# 30000.net
KiCad netlist of a schematic drawn in EasyEDA Pro
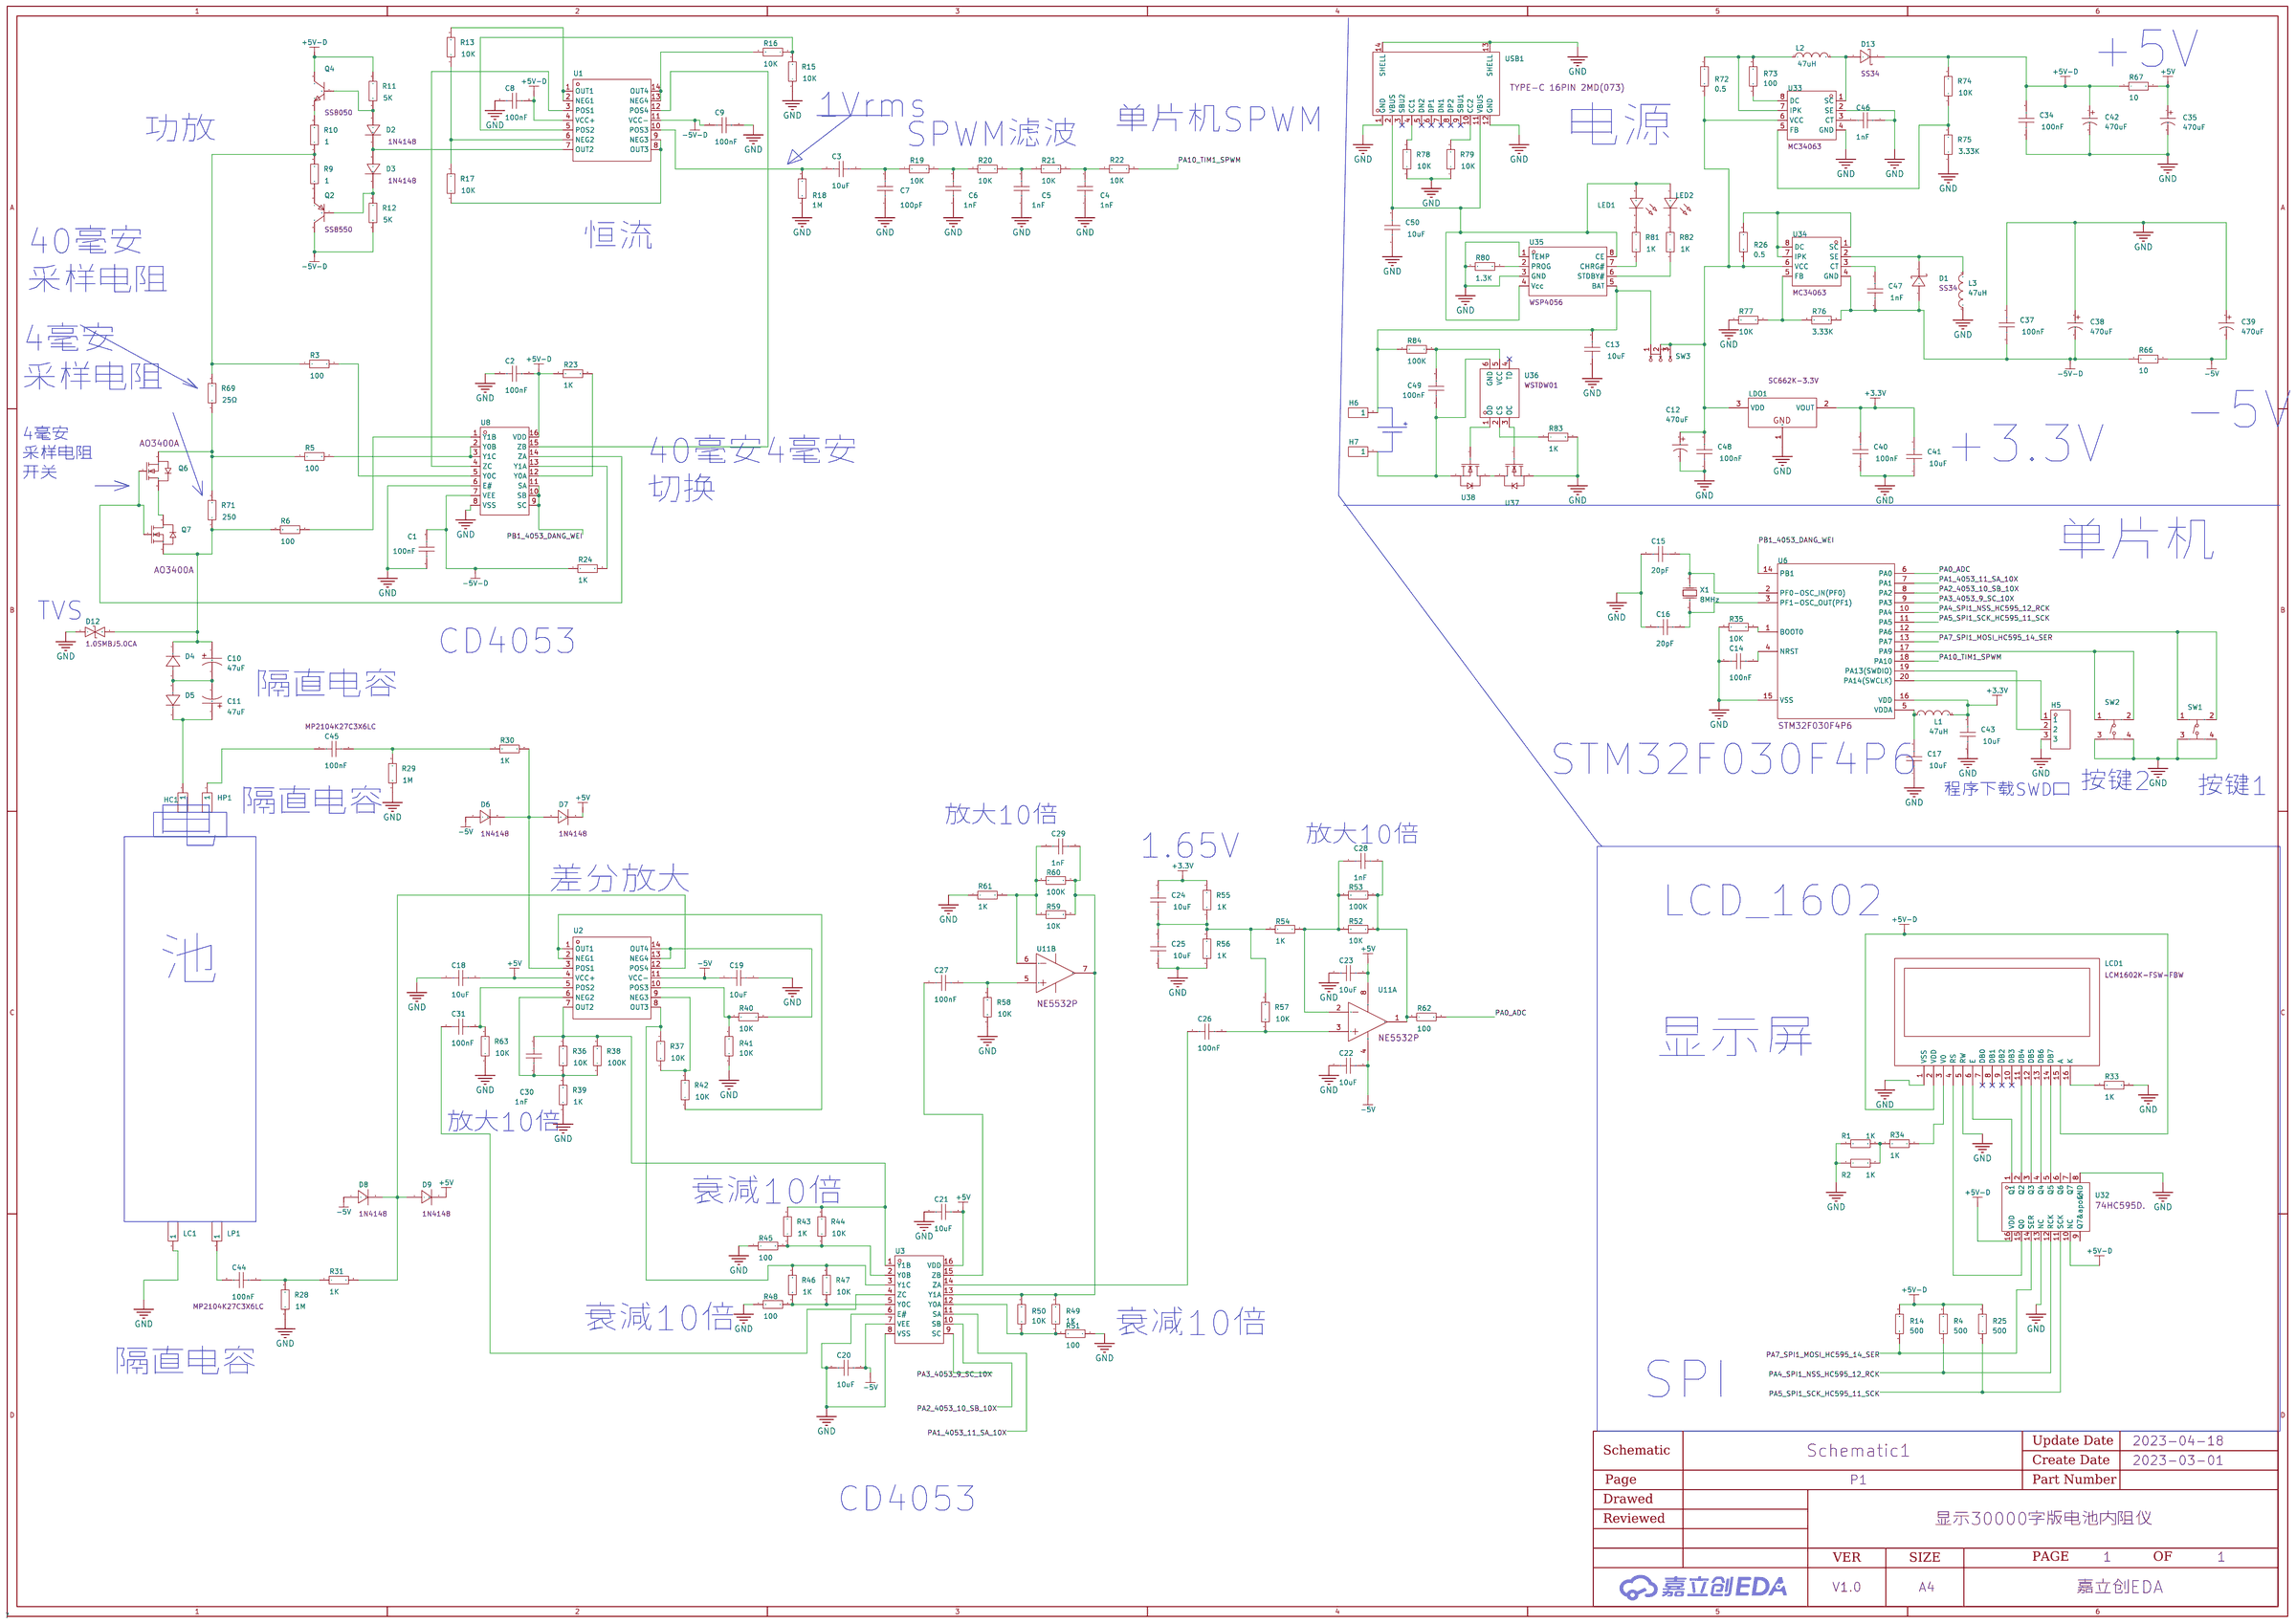
[diagram p0: schematic sheet]

(export (version "E")
  (design (tool "Eeschema 10.0.6"))
  (components
    (comp (ref "C1")
      (value "100nF")
      (footprint "easyedapro:C0603")
      (libsource (lib "easyedapro") (part "CapAcitance"))
    )
    (comp (ref "C2")
      (value "100nF")
      (footprint "easyedapro:C0603")
      (libsource (lib "easyedapro") (part "CapAcitance"))
    )
    (comp (ref "C3")
      (value "10uF")
      (footprint "easyedapro:C0603")
      (libsource (lib "easyedapro") (part "CapAcitance"))
    )
    (comp (ref "C4")
      (value "1nF")
      (footprint "easyedapro:C0603")
      (libsource (lib "easyedapro") (part "CapAcitance"))
    )
    (comp (ref "C5")
      (value "1nF")
      (footprint "easyedapro:C0603")
      (libsource (lib "easyedapro") (part "CapAcitance"))
    )
    (comp (ref "C6")
      (value "1nF")
      (footprint "easyedapro:C0603")
      (libsource (lib "easyedapro") (part "CapAcitance"))
    )
    (comp (ref "C7")
      (value "100pF")
      (footprint "easyedapro:C0603")
      (libsource (lib "easyedapro") (part "CapAcitance"))
    )
    (comp (ref "C8")
      (value "100nF")
      (footprint "easyedapro:C0603")
      (libsource (lib "easyedapro") (part "CapAcitance"))
    )
    (comp (ref "C9")
      (value "100nF")
      (footprint "easyedapro:C0603")
      (libsource (lib "easyedapro") (part "CapAcitance"))
    )
    (comp (ref "C10")
      (value "47uF")
      (footprint "easyedapro:CAP-TH_BD10.0-P5.00-D1.0-FD")
      (description "容值:47uF;精度:±20%;额定电压:200V;电容体直径:10mm;电容体长度:20mm;脚间距:5mm;工作寿命:5000hrs@105°C;")
      (fields (field (name "Manufacturer Part") "KF470M200G200A") (field (name "Manufacturer") "CapXon(丰宾)"))
      (libsource (lib "easyedapro") (part "KF470M200G200A"))
    )
    (comp (ref "C11")
      (value "47uF")
      (footprint "easyedapro:CAP-TH_BD10.0-P5.00-D1.0-FD")
      (description "容值:47uF;精度:±20%;额定电压:200V;电容体直径:10mm;电容体长度:20mm;脚间距:5mm;工作寿命:5000hrs@105°C;")
      (fields (field (name "Manufacturer Part") "KF470M200G200A") (field (name "Manufacturer") "CapXon(丰宾)"))
      (libsource (lib "easyedapro") (part "KF470M200G200A"))
    )
    (comp (ref "C12")
      (value "470uF")
      (footprint "easyedapro:CAP-TH_BD8.0-P3.50-D0.6-FD")
      (description "容值:470uF;精度:±20%;额定电压:16V;电容体直径:8mm;电容体长度:12mm;脚间距:3.5mm;工作寿命:2000hrs@105°C;")
      (fields
        (field (name "Manufacturer Part") "KM477M016F12RR0VH2FP0")
        (field (name "Manufacturer") "CX(承兴)")
      )
      (libsource (lib "easyedapro") (part "470uf16v"))
    )
    (comp (ref "C13")
      (value "10uF")
      (footprint "easyedapro:C0603")
      (libsource (lib "easyedapro") (part "CapAcitance"))
    )
    (comp (ref "C14")
      (value "100nF")
      (footprint "easyedapro:C0603")
      (libsource (lib "easyedapro") (part "CapAcitance"))
    )
    (comp (ref "C15")
      (value "20pF")
      (footprint "easyedapro:C0603")
      (libsource (lib "easyedapro") (part "CapAcitance"))
    )
    (comp (ref "C16")
      (value "20pF")
      (footprint "easyedapro:C0603")
      (libsource (lib "easyedapro") (part "CapAcitance"))
    )
    (comp (ref "C17")
      (value "10uF")
      (footprint "easyedapro:C0603")
      (libsource (lib "easyedapro") (part "CapAcitance"))
    )
    (comp (ref "C18")
      (value "10uF")
      (footprint "easyedapro:C0603")
      (libsource (lib "easyedapro") (part "CapAcitance"))
    )
    (comp (ref "C19")
      (value "10uF")
      (footprint "easyedapro:C0603")
      (libsource (lib "easyedapro") (part "CapAcitance"))
    )
    (comp (ref "C20")
      (value "10uF")
      (footprint "easyedapro:C0603")
      (libsource (lib "easyedapro") (part "CapAcitance"))
    )
    (comp (ref "C21")
      (value "10uF")
      (footprint "easyedapro:C0603")
      (libsource (lib "easyedapro") (part "CapAcitance"))
    )
    (comp (ref "C22")
      (value "10uF")
      (footprint "easyedapro:C0603")
      (libsource (lib "easyedapro") (part "CapAcitance"))
    )
    (comp (ref "C23")
      (value "10uF")
      (footprint "easyedapro:C0603")
      (libsource (lib "easyedapro") (part "CapAcitance"))
    )
    (comp (ref "C24")
      (value "10uF")
      (footprint "easyedapro:C0603")
      (libsource (lib "easyedapro") (part "CapAcitance"))
    )
    (comp (ref "C25")
      (value "10uF")
      (footprint "easyedapro:C0603")
      (libsource (lib "easyedapro") (part "CapAcitance"))
    )
    (comp (ref "C26")
      (value "100nF")
      (footprint "easyedapro:C0603")
      (libsource (lib "easyedapro") (part "CapAcitance"))
    )
    (comp (ref "C27")
      (value "100nF")
      (footprint "easyedapro:C0603")
      (libsource (lib "easyedapro") (part "CapAcitance"))
    )
    (comp (ref "C28")
      (value "1nF")
      (footprint "easyedapro:C0603")
      (libsource (lib "easyedapro") (part "CapAcitance"))
    )
    (comp (ref "C29")
      (value "1nF")
      (footprint "easyedapro:C0603")
      (libsource (lib "easyedapro") (part "CapAcitance"))
    )
    (comp (ref "C30")
      (value "1nF")
      (footprint "easyedapro:C0603")
      (libsource (lib "easyedapro") (part "CapAcitance"))
    )
    (comp (ref "C31")
      (value "100nF")
      (footprint "easyedapro:C0603")
      (libsource (lib "easyedapro") (part "CapAcitance"))
    )
    (comp (ref "C34")
      (value "100nF")
      (footprint "easyedapro:C0603")
      (libsource (lib "easyedapro") (part "CapAcitance"))
    )
    (comp (ref "C35")
      (value "470uF")
      (footprint "easyedapro:CAP-TH_BD8.0-P3.50-D0.6-FD")
      (description "容值:470uF;精度:±20%;额定电压:16V;电容体直径:8mm;电容体长度:12mm;脚间距:3.5mm;工作寿命:2000hrs@105°C;")
      (fields
        (field (name "Manufacturer Part") "KM477M016F12RR0VH2FP0")
        (field (name "Manufacturer") "CX(承兴)")
      )
      (libsource (lib "easyedapro") (part "470uf16v"))
    )
    (comp (ref "C37")
      (value "100nF")
      (footprint "easyedapro:C0603")
      (libsource (lib "easyedapro") (part "CapAcitance"))
    )
    (comp (ref "C38")
      (value "470uF")
      (footprint "easyedapro:CAP-TH_BD8.0-P3.50-D0.6-FD")
      (description "容值:470uF;精度:±20%;额定电压:16V;电容体直径:8mm;电容体长度:12mm;脚间距:3.5mm;工作寿命:2000hrs@105°C;")
      (fields
        (field (name "Manufacturer Part") "KM477M016F12RR0VH2FP0")
        (field (name "Manufacturer") "CX(承兴)")
      )
      (libsource (lib "easyedapro") (part "470uf16v"))
    )
    (comp (ref "C39")
      (value "470uF")
      (footprint "easyedapro:CAP-TH_BD8.0-P3.50-D0.6-FD")
      (description "容值:470uF;精度:±20%;额定电压:16V;电容体直径:8mm;电容体长度:12mm;脚间距:3.5mm;工作寿命:2000hrs@105°C;")
      (fields
        (field (name "Manufacturer Part") "KM477M016F12RR0VH2FP0")
        (field (name "Manufacturer") "CX(承兴)")
      )
      (libsource (lib "easyedapro") (part "470uf16v"))
    )
    (comp (ref "C40")
      (value "100nF")
      (footprint "easyedapro:C0603")
      (libsource (lib "easyedapro") (part "CapAcitance"))
    )
    (comp (ref "C41")
      (value "10uF")
      (footprint "easyedapro:C0603")
      (libsource (lib "easyedapro") (part "CapAcitance"))
    )
    (comp (ref "C42")
      (value "470uF")
      (footprint "easyedapro:CAP-TH_BD8.0-P3.50-D0.6-FD")
      (description "容值:470uF;精度:±20%;额定电压:16V;电容体直径:8mm;电容体长度:12mm;脚间距:3.5mm;工作寿命:2000hrs@105°C;")
      (fields
        (field (name "Manufacturer Part") "KM477M016F12RR0VH2FP0")
        (field (name "Manufacturer") "CX(承兴)")
      )
      (libsource (lib "easyedapro") (part "470uf16v"))
    )
    (comp (ref "C43")
      (value "10uF")
      (footprint "easyedapro:C0603")
      (libsource (lib "easyedapro") (part "CapAcitance"))
    )
    (comp (ref "C44")
      (value "100nF")
      (footprint "easyedapro:CAP-TH_L13.0-W6.0-P10.00-D1.0")
      (description "等级:X2;容值:100nF;精度:±10%;")
      (fields (field (name "Manufacturer Part") "MP2104K27C3X6LC") (field (name "Manufacturer") "SRD(圣融达)"))
      (libsource (lib "easyedapro") (part "MP2104KGC3XLC"))
    )
    (comp (ref "C45")
      (value "100nF")
      (footprint "easyedapro:CAP-TH_L13.0-W6.0-P10.00-D1.0")
      (description "等级:X2;容值:100nF;精度:±10%;")
      (fields (field (name "Manufacturer Part") "MP2104K27C3X6LC") (field (name "Manufacturer") "SRD(圣融达)"))
      (libsource (lib "easyedapro") (part "MP2104KGC3XLC"))
    )
    (comp (ref "C46")
      (value "1nF")
      (footprint "easyedapro:C0603")
      (libsource (lib "easyedapro") (part "CapAcitance"))
    )
    (comp (ref "C47")
      (value "1nF")
      (footprint "easyedapro:C0603")
      (libsource (lib "easyedapro") (part "CapAcitance"))
    )
    (comp (ref "C48")
      (value "100nF")
      (footprint "easyedapro:C0603")
      (libsource (lib "easyedapro") (part "CapAcitance"))
    )
    (comp (ref "C49")
      (value "100nF")
      (footprint "easyedapro:C0603")
      (libsource (lib "easyedapro") (part "CapAcitance"))
    )
    (comp (ref "C50")
      (value "10uF")
      (footprint "easyedapro:C0603")
      (libsource (lib "easyedapro") (part "CapAcitance"))
    )
    (comp (ref "D1")
      (value "SS34")
      (footprint "easyedapro:SMA_L4.3-W2.6-LS5.2-RD")
      (description "二极管配置:独立式;直流反向耐压(Vr):40V;平均整流电流(Io):3A;正向压降(Vf):550mV@3A;反向电流(Ir):500uA@40V;")
      (fields (field (name "Manufacturer Part") "SS34") (field (name "Manufacturer") "MDD"))
      (libsource (lib "easyedapro") (part "SS34_C8678"))
    )
    (comp (ref "D2")
      (value "1N4148")
      (footprint "easyedapro:DO-35_BD2.0-L4.0-P8.00-D0.5-FD")
      (fields (field (name "Manufacturer Part") "1N4148") (field (name "Manufacturer") "ST(先科)"))
      (libsource (lib "easyedapro") (part "1N4148"))
    )
    (comp (ref "D3")
      (value "1N4148")
      (footprint "easyedapro:DO-35_BD2.0-L4.0-P8.00-D0.5-FD")
      (fields (field (name "Manufacturer Part") "1N4148") (field (name "Manufacturer") "ST(先科)"))
      (libsource (lib "easyedapro") (part "1N4148"))
    )
    (comp (ref "D4")
      (value "~")
      (footprint "easyedapro:DO_1N4007")
      (libsource (lib "easyedapro") (part "D_1N4007"))
    )
    (comp (ref "D5")
      (value "~")
      (footprint "easyedapro:DO_1N4007")
      (libsource (lib "easyedapro") (part "D_1N4007"))
    )
    (comp (ref "D6")
      (value "1N4148")
      (footprint "easyedapro:DO-35_BD2.0-L4.0-P8.00-D0.5-FD")
      (fields (field (name "Manufacturer Part") "1N4148") (field (name "Manufacturer") "ST(先科)"))
      (libsource (lib "easyedapro") (part "1N4148"))
    )
    (comp (ref "D7")
      (value "1N4148")
      (footprint "easyedapro:DO-35_BD2.0-L4.0-P8.00-D0.5-FD")
      (fields (field (name "Manufacturer Part") "1N4148") (field (name "Manufacturer") "ST(先科)"))
      (libsource (lib "easyedapro") (part "1N4148"))
    )
    (comp (ref "D8")
      (value "1N4148")
      (footprint "easyedapro:DO-35_BD2.0-L4.0-P8.00-D0.5-FD")
      (fields (field (name "Manufacturer Part") "1N4148") (field (name "Manufacturer") "ST(先科)"))
      (libsource (lib "easyedapro") (part "1N4148"))
    )
    (comp (ref "D9")
      (value "1N4148")
      (footprint "easyedapro:DO-35_BD2.0-L4.0-P8.00-D0.5-FD")
      (fields (field (name "Manufacturer Part") "1N4148") (field (name "Manufacturer") "ST(先科)"))
      (libsource (lib "easyedapro") (part "1N4148"))
    )
    (comp (ref "D12")
      (value "1.0SMBJ5.0CA")
      (footprint "easyedapro:SMB_L4.6-W3.6-LS5.3-BI")
      (description "极性:双向;反向截止电压(Vrwm):5V;击穿电压:6.4V;峰值脉冲电流(Ipp)@10/1000s:108.7A;最大钳位电压:9.2V;")
      (fields (field (name "Manufacturer Part") "1.0SMBJ5.0CA") (field (name "Manufacturer") "BORN(伯恩半导体)"))
      (libsource (lib "easyedapro") (part "1.0SMBJ5.0CA"))
    )
    (comp (ref "D13")
      (value "SS34")
      (footprint "easyedapro:SMA_L4.3-W2.6-LS5.2-RD")
      (description "二极管配置:独立式;直流反向耐压(Vr):40V;平均整流电流(Io):3A;正向压降(Vf):550mV@3A;反向电流(Ir):500uA@40V;")
      (fields (field (name "Manufacturer Part") "SS34") (field (name "Manufacturer") "MDD"))
      (libsource (lib "easyedapro") (part "SS34_C8678"))
    )
    (comp (ref "H5")
      (value "~")
      (footprint "easyedapro:HDR-TH_3P-P2.54-V-M")
      (libsource (lib "easyedapro") (part "PZ254V-11-03P_C2937625"))
    )
    (comp (ref "H6")
      (value "~")
      (footprint "easyedapro:HDR-TH_1P-V-M_XKB_X4611WV-01I-C28D40")
      (libsource (lib "easyedapro") (part "HDR_1x1"))
    )
    (comp (ref "H7")
      (value "~")
      (footprint "easyedapro:HDR-TH_1P-V-M_XKB_X4611WV-01I-C28D40")
      (libsource (lib "easyedapro") (part "HDR_1x1"))
    )
    (comp (ref "HC1")
      (value "~")
      (footprint "easyedapro:HDR-TH_1P-V-M_XKB_X4611WV-01I-C28D40")
      (libsource (lib "easyedapro") (part "HDR_1x1"))
    )
    (comp (ref "HP1")
      (value "~")
      (footprint "easyedapro:HDR-TH_1P-V-M_XKB_X4611WV-01I-C28D40")
      (libsource (lib "easyedapro") (part "HDR_1x1"))
    )
    (comp (ref "L1")
      (value "47uH")
      (footprint "easyedapro:IND-SMD_L4.5-W4.0_SLF0403")
      (description "电感值:47uH;直流电阻(DCR):844mΩ;精度:±10%;额定电流:540mA;")
      (fields
        (field (name "Manufacturer Part") "SLF0403-470KTT")
        (field (name "Manufacturer") "Sunltech(韩国顺磁)")
      )
      (libsource (lib "easyedapro") (part "SLF0403-470KTT"))
    )
    (comp (ref "L2")
      (value "47uH")
      (footprint "easyedapro:IND-SMD_L4.5-W4.0_SLF0403")
      (description "电感值:47uH;直流电阻(DCR):844mΩ;精度:±10%;额定电流:540mA;")
      (fields
        (field (name "Manufacturer Part") "SLF0403-470KTT")
        (field (name "Manufacturer") "Sunltech(韩国顺磁)")
      )
      (libsource (lib "easyedapro") (part "SLF0403-470KTT"))
    )
    (comp (ref "L3")
      (value "47uH")
      (footprint "easyedapro:IND-SMD_L4.5-W4.0_SLF0403")
      (description "电感值:47uH;直流电阻(DCR):844mΩ;精度:±10%;额定电流:540mA;")
      (fields
        (field (name "Manufacturer Part") "SLF0403-470KTT")
        (field (name "Manufacturer") "Sunltech(韩国顺磁)")
      )
      (libsource (lib "easyedapro") (part "SLF0403-470KTT"))
    )
    (comp (ref "LC1")
      (value "~")
      (footprint "easyedapro:HDR-TH_1P-V-M_XKB_X4611WV-01I-C28D40")
      (libsource (lib "easyedapro") (part "HDR_1x1"))
    )
    (comp (ref "LCD1")
      (value "LCM1602K-FSW-FBW")
      (footprint "easyedapro:MODULE-TH_LCM1602K")
      (description "尺寸(inch):-;主控芯片:KS0066U;")
      (fields
        (field (name "Manufacturer Part") "LCM1602K-FSW-FBW")
        (field (name "Manufacturer") "LONTECH(厦门龙特)")
      )
      (libsource (lib "easyedapro") (part "LCM1602K-FSW-FBW"))
    )
    (comp (ref "LDO1")
      (value "SC662K-3.3V")
      (footprint "easyedapro:SOT-23-3_L2.9-W1.3-P1.90-LS2.4-BR")
      (description "输出类型:固定;输出极性:正;最大输入电压:6V;输出电压:3.3V;输出电流:250mA;电源纹波抑制比(PSRR):50dB@(1kHz);")
      (fields (field (name "Manufacturer Part") "SC662K-3.3V") (field (name "Manufacturer") "FM(富满)"))
      (libsource (lib "easyedapro") (part "SC662K-3.3V"))
    )
    (comp (ref "LED1")
      (value "~")
      (footprint "easyedapro:LED_TH-3mm")
      (libsource (lib "easyedapro") (part "LED_TH-R"))
    )
    (comp (ref "LED2")
      (value "~")
      (footprint "easyedapro:LED_TH-3mm")
      (libsource (lib "easyedapro") (part "LED_TH-R"))
    )
    (comp (ref "LP1")
      (value "~")
      (footprint "easyedapro:HDR-TH_1P-V-M_XKB_X4611WV-01I-C28D40")
      (libsource (lib "easyedapro") (part "HDR_1x1"))
    )
    (comp (ref "Q2")
      (value "SS8550")
      (footprint "easyedapro:SOT-23-3_L2.9-W1.6-P1.90-LS2.8-BR")
      (fields (field (name "Manufacturer Part") "SS8550") (field (name "Manufacturer") "ElecSuper(静芯微）"))
      (libsource (lib "easyedapro") (part "SS8550_C5249677"))
    )
    (comp (ref "Q4")
      (value "SS8050")
      (footprint "easyedapro:SOT-23-3_L2.9-W1.6-P1.90-LS2.8-BR")
      (fields (field (name "Manufacturer Part") "SS8050") (field (name "Manufacturer") "ElecSuper(静芯微）"))
      (libsource (lib "easyedapro") (part "SS8050_C5249676"))
    )
    (comp (ref "Q6")
      (value "AO3400A")
      (footprint "easyedapro:SOT-23-3_L2.9-W1.3-P1.90-LS2.4-BR")
      (fields (field (name "Manufacturer Part") "AO3400A") (field (name "Manufacturer") "UMW(广东友台半导体)"))
      (libsource (lib "easyedapro") (part "AO3400A_C347475"))
    )
    (comp (ref "Q7")
      (value "AO3400A")
      (footprint "easyedapro:SOT-23-3_L2.9-W1.3-P1.90-LS2.4-BR")
      (fields (field (name "Manufacturer Part") "AO3400A") (field (name "Manufacturer") "UMW(广东友台半导体)"))
      (libsource (lib "easyedapro") (part "AO3400A_C347475"))
    )
    (comp (ref "R1")
      (value "1K")
      (footprint "easyedapro:Res_1/8W")
      (libsource (lib "easyedapro") (part "电阻"))
    )
    (comp (ref "R2")
      (value "1K")
      (footprint "easyedapro:Res_1/8W")
      (libsource (lib "easyedapro") (part "电阻"))
    )
    (comp (ref "R3")
      (value "100")
      (footprint "easyedapro:Res_1/8W")
      (libsource (lib "easyedapro") (part "电阻"))
    )
    (comp (ref "R4")
      (value "500")
      (footprint "easyedapro:Res_1/8W")
      (libsource (lib "easyedapro") (part "电阻"))
    )
    (comp (ref "R5")
      (value "100")
      (footprint "easyedapro:Res_1/8W")
      (libsource (lib "easyedapro") (part "电阻"))
    )
    (comp (ref "R6")
      (value "100")
      (footprint "easyedapro:Res_1/8W")
      (libsource (lib "easyedapro") (part "电阻"))
    )
    (comp (ref "R9") (value "1") (footprint "easyedapro:Res_1/8W") (libsource (lib "easyedapro") (part "电阻")))
    (comp (ref "R10")
      (value "1")
      (footprint "easyedapro:Res_1/8W")
      (libsource (lib "easyedapro") (part "电阻"))
    )
    (comp (ref "R11")
      (value "5K")
      (footprint "easyedapro:Res_1/8W")
      (libsource (lib "easyedapro") (part "电阻"))
    )
    (comp (ref "R12")
      (value "5K")
      (footprint "easyedapro:Res_1/8W")
      (libsource (lib "easyedapro") (part "电阻"))
    )
    (comp (ref "R13")
      (value "10K")
      (footprint "easyedapro:Res_1/8W")
      (libsource (lib "easyedapro") (part "电阻"))
    )
    (comp (ref "R14")
      (value "500")
      (footprint "easyedapro:Res_1/8W")
      (libsource (lib "easyedapro") (part "电阻"))
    )
    (comp (ref "R15")
      (value "10K")
      (footprint "easyedapro:Res_1/8W")
      (libsource (lib "easyedapro") (part "电阻"))
    )
    (comp (ref "R16")
      (value "10K")
      (footprint "easyedapro:Res_1/8W")
      (libsource (lib "easyedapro") (part "电阻"))
    )
    (comp (ref "R17")
      (value "10K")
      (footprint "easyedapro:Res_1/8W")
      (libsource (lib "easyedapro") (part "电阻"))
    )
    (comp (ref "R18")
      (value "1M")
      (footprint "easyedapro:Res_1/8W")
      (libsource (lib "easyedapro") (part "电阻"))
    )
    (comp (ref "R19")
      (value "10K")
      (footprint "easyedapro:Res_1/8W")
      (libsource (lib "easyedapro") (part "电阻"))
    )
    (comp (ref "R20")
      (value "10K")
      (footprint "easyedapro:Res_1/8W")
      (libsource (lib "easyedapro") (part "电阻"))
    )
    (comp (ref "R21")
      (value "10K")
      (footprint "easyedapro:Res_1/8W")
      (libsource (lib "easyedapro") (part "电阻"))
    )
    (comp (ref "R22")
      (value "10K")
      (footprint "easyedapro:Res_1/8W")
      (libsource (lib "easyedapro") (part "电阻"))
    )
    (comp (ref "R23")
      (value "1K")
      (footprint "easyedapro:Res_1/8W")
      (libsource (lib "easyedapro") (part "电阻"))
    )
    (comp (ref "R24")
      (value "1K")
      (footprint "easyedapro:Res_1/8W")
      (libsource (lib "easyedapro") (part "电阻"))
    )
    (comp (ref "R25")
      (value "500")
      (footprint "easyedapro:Res_1/8W")
      (libsource (lib "easyedapro") (part "电阻"))
    )
    (comp (ref "R26") (value "0.5") (footprint "easyedapro:R0603") (libsource (lib "easyedapro") (part "电阻")))
    (comp (ref "R28")
      (value "1M")
      (footprint "easyedapro:Res_1/8W")
      (libsource (lib "easyedapro") (part "电阻"))
    )
    (comp (ref "R29")
      (value "1M")
      (footprint "easyedapro:Res_1/8W")
      (libsource (lib "easyedapro") (part "电阻"))
    )
    (comp (ref "R30")
      (value "1K")
      (footprint "easyedapro:Res_1/8W")
      (libsource (lib "easyedapro") (part "电阻"))
    )
    (comp (ref "R31")
      (value "1K")
      (footprint "easyedapro:Res_1/8W")
      (libsource (lib "easyedapro") (part "电阻"))
    )
    (comp (ref "R33")
      (value "1K")
      (footprint "easyedapro:Res_1/8W")
      (libsource (lib "easyedapro") (part "电阻"))
    )
    (comp (ref "R34")
      (value "1K")
      (footprint "easyedapro:Res_1/8W")
      (libsource (lib "easyedapro") (part "电阻"))
    )
    (comp (ref "R35")
      (value "10K")
      (footprint "easyedapro:Res_1/8W")
      (libsource (lib "easyedapro") (part "电阻"))
    )
    (comp (ref "R36")
      (value "10K")
      (footprint "easyedapro:Res_1/8W")
      (libsource (lib "easyedapro") (part "电阻"))
    )
    (comp (ref "R37")
      (value "10K")
      (footprint "easyedapro:Res_1/8W")
      (libsource (lib "easyedapro") (part "电阻"))
    )
    (comp (ref "R38")
      (value "100K")
      (footprint "easyedapro:Res_1/8W")
      (libsource (lib "easyedapro") (part "电阻"))
    )
    (comp (ref "R39")
      (value "1K")
      (footprint "easyedapro:Res_1/8W")
      (libsource (lib "easyedapro") (part "电阻"))
    )
    (comp (ref "R40")
      (value "10K")
      (footprint "easyedapro:Res_1/8W")
      (libsource (lib "easyedapro") (part "电阻"))
    )
    (comp (ref "R41")
      (value "10K")
      (footprint "easyedapro:Res_1/8W")
      (libsource (lib "easyedapro") (part "电阻"))
    )
    (comp (ref "R42")
      (value "10K")
      (footprint "easyedapro:Res_1/8W")
      (libsource (lib "easyedapro") (part "电阻"))
    )
    (comp (ref "R43")
      (value "1K")
      (footprint "easyedapro:Res_1/8W")
      (libsource (lib "easyedapro") (part "电阻"))
    )
    (comp (ref "R44")
      (value "10K")
      (footprint "easyedapro:Res_1/8W")
      (libsource (lib "easyedapro") (part "电阻"))
    )
    (comp (ref "R45")
      (value "100")
      (footprint "easyedapro:Res_1/8W")
      (libsource (lib "easyedapro") (part "电阻"))
    )
    (comp (ref "R46")
      (value "1K")
      (footprint "easyedapro:Res_1/8W")
      (libsource (lib "easyedapro") (part "电阻"))
    )
    (comp (ref "R47")
      (value "10K")
      (footprint "easyedapro:Res_1/8W")
      (libsource (lib "easyedapro") (part "电阻"))
    )
    (comp (ref "R48")
      (value "100")
      (footprint "easyedapro:Res_1/8W")
      (libsource (lib "easyedapro") (part "电阻"))
    )
    (comp (ref "R49")
      (value "1K")
      (footprint "easyedapro:Res_1/8W")
      (libsource (lib "easyedapro") (part "电阻"))
    )
    (comp (ref "R50")
      (value "10K")
      (footprint "easyedapro:Res_1/8W")
      (libsource (lib "easyedapro") (part "电阻"))
    )
    (comp (ref "R51")
      (value "100")
      (footprint "easyedapro:Res_1/8W")
      (libsource (lib "easyedapro") (part "电阻"))
    )
    (comp (ref "R52")
      (value "10K")
      (footprint "easyedapro:Res_1/8W")
      (libsource (lib "easyedapro") (part "电阻"))
    )
    (comp (ref "R53")
      (value "100K")
      (footprint "easyedapro:Res_1/8W")
      (libsource (lib "easyedapro") (part "电阻"))
    )
    (comp (ref "R54")
      (value "1K")
      (footprint "easyedapro:Res_1/8W")
      (libsource (lib "easyedapro") (part "电阻"))
    )
    (comp (ref "R55")
      (value "1K")
      (footprint "easyedapro:Res_1/8W")
      (libsource (lib "easyedapro") (part "电阻"))
    )
    (comp (ref "R56")
      (value "1K")
      (footprint "easyedapro:Res_1/8W")
      (libsource (lib "easyedapro") (part "电阻"))
    )
    (comp (ref "R57")
      (value "10K")
      (footprint "easyedapro:Res_1/8W")
      (libsource (lib "easyedapro") (part "电阻"))
    )
    (comp (ref "R58")
      (value "10K")
      (footprint "easyedapro:Res_1/8W")
      (libsource (lib "easyedapro") (part "电阻"))
    )
    (comp (ref "R59")
      (value "10K")
      (footprint "easyedapro:Res_1/8W")
      (libsource (lib "easyedapro") (part "电阻"))
    )
    (comp (ref "R60")
      (value "100K")
      (footprint "easyedapro:Res_1/8W")
      (libsource (lib "easyedapro") (part "电阻"))
    )
    (comp (ref "R61")
      (value "1K")
      (footprint "easyedapro:Res_1/8W")
      (libsource (lib "easyedapro") (part "电阻"))
    )
    (comp (ref "R62")
      (value "100")
      (footprint "easyedapro:Res_1/8W")
      (libsource (lib "easyedapro") (part "电阻"))
    )
    (comp (ref "R63")
      (value "10K")
      (footprint "easyedapro:Res_1/8W")
      (libsource (lib "easyedapro") (part "电阻"))
    )
    (comp (ref "R66") (value "10") (footprint "easyedapro:R0603") (libsource (lib "easyedapro") (part "电阻")))
    (comp (ref "R67") (value "10") (footprint "easyedapro:R0603") (libsource (lib "easyedapro") (part "电阻")))
    (comp (ref "R69")
      (value "25Ω")
      (footprint "easyedapro:R2512")
      (description "电阻类型:厚膜电阻;阻值:10Ω;精度:±5%;功率:2W;温度系数:±200ppm/°C;最大工作电压:200V;工作温度范围:-55°C~+155°C;")
      (fields (field (name "Manufacturer Part") "RC2512JK-7W10RL") (field (name "Manufacturer") "YAGEO(国巨)"))
      (libsource (lib "easyedapro") (part "RC2512JK-7W10RL"))
    )
    (comp (ref "R71")
      (value "250")
      (footprint "easyedapro:R0603")
      (description "电阻类型:厚膜电阻;阻值:100Ω;精度:±1%;功率:100mW;温度系数:±100ppm/°C;最大工作电压:75V;工作温度范围:-55°C~+155°C;")
      (fields (field (name "Manufacturer Part") "AC0603FR-07100RL") (field (name "Manufacturer") "YAGEO(国巨)"))
      (libsource (lib "easyedapro") (part "AC0603FR-07100RL"))
    )
    (comp (ref "R72") (value "0.5") (footprint "easyedapro:R0603") (libsource (lib "easyedapro") (part "电阻")))
    (comp (ref "R73") (value "100") (footprint "easyedapro:R0603") (libsource (lib "easyedapro") (part "电阻")))
    (comp (ref "R74") (value "10K") (footprint "easyedapro:R0603") (libsource (lib "easyedapro") (part "电阻")))
    (comp (ref "R75")
      (value "3.33K")
      (footprint "easyedapro:R0603")
      (libsource (lib "easyedapro") (part "电阻"))
    )
    (comp (ref "R76")
      (value "3.33K")
      (footprint "easyedapro:R0603")
      (libsource (lib "easyedapro") (part "电阻"))
    )
    (comp (ref "R77") (value "10K") (footprint "easyedapro:R0603") (libsource (lib "easyedapro") (part "电阻")))
    (comp (ref "R78") (value "10K") (footprint "easyedapro:R0603") (libsource (lib "easyedapro") (part "电阻")))
    (comp (ref "R79") (value "10K") (footprint "easyedapro:R0603") (libsource (lib "easyedapro") (part "电阻")))
    (comp (ref "R80")
      (value "1.3K")
      (footprint "easyedapro:R0603")
      (libsource (lib "easyedapro") (part "电阻"))
    )
    (comp (ref "R81") (value "1K") (footprint "easyedapro:R0603") (libsource (lib "easyedapro") (part "电阻")))
    (comp (ref "R82") (value "1K") (footprint "easyedapro:R0603") (libsource (lib "easyedapro") (part "电阻")))
    (comp (ref "R83") (value "1K") (footprint "easyedapro:R0603") (libsource (lib "easyedapro") (part "电阻")))
    (comp (ref "R84")
      (value "100K")
      (footprint "easyedapro:R0603")
      (libsource (lib "easyedapro") (part "电阻"))
    )
    (comp (ref "SW1")
      (value "1TS005A-2600-5001")
      (footprint "easyedapro:SW-TH_4P-L6.0-W6.0-P4.50-LS6.5")
      (fields (field (name "Manufacturer") "HYP(鸿源精密)"))
      (libsource (lib "easyedapro") (part "1TS005A-2600-5001"))
    )
    (comp (ref "SW2")
      (value "1TS005A-2600-5001")
      (footprint "easyedapro:SW-TH_4P-L6.0-W6.0-P4.50-LS6.5")
      (fields (field (name "Manufacturer") "HYP(鸿源精密)"))
      (libsource (lib "easyedapro") (part "1TS005A-2600-5001"))
    )
    (comp (ref "SW3")
      (value "SS-12F20-G070")
      (footprint "easyedapro:SW-TH_G-SWITCH_SS-12F20-G070")
      (fields (field (name "Manufacturer") "G-Switch(品赞)"))
      (libsource (lib "easyedapro") (part "SS-12F20-G070"))
    )
    (comp (ref "U1")
      (value "TL084CN")
      (footprint "easyedapro:DIP-14_L17.8-W10.2-P2.54-BL")
      (description "运放类型:J-FET;放大器组数:4;增益带宽积（GBP）:4MHz;压摆率（SR）:16 V/us;电源电压:6V ~ 36V, ±3V ~ 18V;各通道供电电流:1.4mA;")
      (fields (field (name "Manufacturer") "TI(德州仪器)"))
      (libsource (lib "easyedapro") (part "TL084CN_C54501"))
    )
    (comp (ref "U2")
      (value "TL084CN")
      (footprint "easyedapro:DIP-14_L17.8-W10.2-P2.54-BL")
      (description "运放类型:J-FET;放大器组数:4;增益带宽积（GBP）:4MHz;压摆率（SR）:16 V/us;电源电压:6V ~ 36V, ±3V ~ 18V;各通道供电电流:1.4mA;")
      (fields (field (name "Manufacturer") "TI(德州仪器)"))
      (libsource (lib "easyedapro") (part "TL084CN_C54501"))
    )
    (comp (ref "U3")
      (value "CD4053BM/TR")
      (footprint "easyedapro:SOP-16_L9.9-W3.9-P1.27-LS6.1-BL")
      (fields (field (name "Manufacturer") "HGSEMI(华冠)"))
      (libsource (lib "easyedapro") (part "CD4053BM/TR"))
    )
    (comp (ref "U6")
      (value "STM32F030F4P6")
      (footprint "easyedapro:TSSOP-20_L6.5-W4.4-P0.65-LS6.4-BL")
      (fields (field (name "Manufacturer Part") "STM32F030F4P6") (field (name "Manufacturer") "ST(意法半导体)"))
      (libsource (lib "easyedapro") (part "STM32F030F4P6"))
    )
    (comp (ref "U8")
      (value "CD4053BM/TR")
      (footprint "easyedapro:SOP-16_L9.9-W3.9-P1.27-LS6.1-BL")
      (fields (field (name "Manufacturer") "HGSEMI(华冠)"))
      (libsource (lib "easyedapro") (part "CD4053BM/TR"))
    )
    (comp (ref "U11")
      (value "NE5532P")
      (footprint "easyedapro:DIP-8_L9.4-W6.4-P2.54-LS9.1-BL")
      (description "运放类型:General Purpose;放大器组数:2;增益带宽积（GBP）:10MHz;压摆率（SR）:9 V/us;电源电压:±5V ~ 15V;各通道供电电流:8mA;")
      (fields (field (name "Manufacturer Part") "NE5532P") (field (name "Manufacturer") "TI(德州仪器)"))
      (libsource (lib "easyedapro") (part "NE5532P"))
    )
    (comp (ref "U32")
      (value "74HC595D.")
      (footprint "easyedapro:SOP-16_L9.9-W3.9-P1.27-LS6.0-BL")
      (fields (field (name "Manufacturer Part") "74HC595D.") (field (name "Manufacturer") "FM(富满)"))
      (libsource (lib "easyedapro") (part "74HC595D."))
    )
    (comp (ref "U33")
      (value "MC34063")
      (footprint "easyedapro:SOIC-8_L5.0-W4.0-P1.27-LS6.0-BL")
      (fields (field (name "Manufacturer Part") "MC34063") (field (name "Manufacturer") "HXY MOSFET(华轩阳电子)"))
      (libsource (lib "easyedapro") (part "MC34063_C5349988"))
    )
    (comp (ref "U34")
      (value "MC34063")
      (footprint "easyedapro:SOIC-8_L5.0-W4.0-P1.27-LS6.0-BL")
      (fields (field (name "Manufacturer Part") "MC34063") (field (name "Manufacturer") "HXY MOSFET(华轩阳电子)"))
      (libsource (lib "easyedapro") (part "MC34063_C5349988"))
    )
    (comp (ref "U35")
      (value "WSP4056")
      (footprint "easyedapro:SOP-8_L5.1-W3.9-P1.27-LS6.0-BL")
      (fields (field (name "Manufacturer Part") "WSP4056") (field (name "Manufacturer") "WINSOK(微硕)"))
      (libsource (lib "easyedapro") (part "WSP4056"))
    )
    (comp (ref "U36")
      (value "WSTDW01")
      (footprint "easyedapro:SOT-23-6_L2.9-W1.6-P0.95-LS2.8-BR")
      (description "充电电池的类型:-;电池单元组数:-;最大充电电流:-;充满的电池组电压:-;最大供应电压:-;")
      (fields (field (name "Manufacturer Part") "WSTDW01") (field (name "Manufacturer") "WINSOK(微硕)"))
      (libsource (lib "easyedapro") (part "WSTDW01"))
    )
    (comp (ref "U37")
      (value "AO3400A")
      (footprint "easyedapro:SOT-23-3_L3.0-W1.6-P1.90-LS2.8-BR")
      (fields (field (name "Manufacturer") "ElecSuper(静芯微）"))
      (libsource (lib "easyedapro") (part "AO3400A_C5224194"))
    )
    (comp (ref "U38")
      (value "AO3400A")
      (footprint "easyedapro:SOT-23-3_L3.0-W1.6-P1.90-LS2.8-BR")
      (fields (field (name "Manufacturer") "ElecSuper(静芯微）"))
      (libsource (lib "easyedapro") (part "AO3400A_C5224194"))
    )
    (comp (ref "USB1")
      (value "TYPE-C 16PIN 2MD(073)")
      (footprint "easyedapro:USB-C-SMD_TYPE-C-6PIN-2MD-073")
      (description "连接器类型:Type-C;标准:-;公母:母座;触点数量:16;端口数量:1;安装方式:卧贴;额定电流 - 电源:5A;工作温度范围:-25°C~+85°C;")
      (fields
        (field (name "Manufacturer Part") "TYPE-C 16PIN 2MD(073)")
        (field (name "Manufacturer") "SHOU HAN(首韩)")
      )
      (libsource (lib "easyedapro") (part "TYPE-C 16PIN 2MD(073)"))
    )
    (comp (ref "X1")
      (value "8MHz")
      (footprint "easyedapro:OSC-TH_L10.0-W4.5-P5.00")
      (description "晶振类型:49S晶振;频率:8MHz;频率公差:±20ppm;频率稳定度:±30ppm;负载电容:20pF;工作温度:-20°C~+70°C;")
      (fields (field (name "Manufacturer Part") "X49SD8MSD2SC") (field (name "Manufacturer") "YXC(扬兴晶振)"))
      (libsource (lib "easyedapro") (part "X49SD8MSD2SC"))
    )
  )
  (nets
    (net (code "1") (name "+3.3V") (class "Default")
      (node (ref "C24") (pin "2") (pinfunction "2_2") (pintype "input"))
      (node (ref "C40") (pin "2") (pinfunction "2_2") (pintype "input"))
      (node (ref "C41") (pin "2") (pinfunction "2_2") (pintype "input"))
      (node (ref "C43") (pin "2") (pinfunction "2_2") (pintype "input"))
      (node (ref "L1") (pin "2") (pinfunction "2_2") (pintype "input"))
      (node (ref "LDO1") (pin "2") (pinfunction "VOUT_2") (pintype "input"))
      (node (ref "R55") (pin "2") (pinfunction "2_2") (pintype "input"))
      (node (ref "U6") (pin "16") (pinfunction "VDD_16") (pintype "input"))
    )
    (net (code "2") (name "+5V") (class "Default")
      (node (ref "C18") (pin "2") (pinfunction "2_2") (pintype "input"))
      (node (ref "C21") (pin "2") (pinfunction "2_2") (pintype "input"))
      (node (ref "C23") (pin "2") (pinfunction "2_2") (pintype "input"))
      (node (ref "C35") (pin "1") (pinfunction "1_1") (pintype "input"))
      (node (ref "D7") (pin "2") (pinfunction "C_2") (pintype "input"))
      (node (ref "D9") (pin "2") (pinfunction "C_2") (pintype "input"))
      (node (ref "R67") (pin "2") (pinfunction "2_2") (pintype "input"))
      (node (ref "U11") (pin "8") (pinfunction "VCC+_8") (pintype "input"))
      (node (ref "U2") (pin "4") (pinfunction "VCC+_4") (pintype "input"))
      (node (ref "U3") (pin "16") (pinfunction "VDD_16") (pintype "input"))
    )
    (net (code "3") (name "+5V-D") (class "Default")
      (node (ref "C2") (pin "2") (pinfunction "2_2") (pintype "input"))
      (node (ref "C34") (pin "2") (pinfunction "2_2") (pintype "input"))
      (node (ref "C42") (pin "1") (pinfunction "1_1") (pintype "input"))
      (node (ref "C8") (pin "2") (pinfunction "2_2") (pintype "input"))
      (node (ref "D13") (pin "1") (pinfunction "K_1") (pintype "input"))
      (node (ref "LCD1") (pin "15") (pinfunction "A_15") (pintype "input"))
      (node (ref "LCD1") (pin "2") (pinfunction "VDD_2") (pintype "input"))
      (node (ref "Q4") (pin "3") (pinfunction "C_3") (pintype "input"))
      (node (ref "R11") (pin "2") (pinfunction "2_2") (pintype "input"))
      (node (ref "R14") (pin "2") (pinfunction "2_2") (pintype "input"))
      (node (ref "R23") (pin "1") (pinfunction "1_1") (pintype "input"))
      (node (ref "R25") (pin "2") (pinfunction "2_2") (pintype "input"))
      (node (ref "R4") (pin "2") (pinfunction "2_2") (pintype "input"))
      (node (ref "R67") (pin "1") (pinfunction "1_1") (pintype "input"))
      (node (ref "R74") (pin "2") (pinfunction "2_2") (pintype "input"))
      (node (ref "U1") (pin "4") (pinfunction "VCC+_4") (pintype "input"))
      (node (ref "U32") (pin "10") (pinfunction "NC_10") (pintype "input"))
      (node (ref "U32") (pin "16") (pinfunction "VDD_16") (pintype "input"))
      (node (ref "U8") (pin "16") (pinfunction "VDD_16") (pintype "input"))
    )
    (net (code "4") (name "-5V") (class "Default")
      (node (ref "C19") (pin "1") (pinfunction "1_1") (pintype "input"))
      (node (ref "C20") (pin "2") (pinfunction "2_2") (pintype "input"))
      (node (ref "C22") (pin "2") (pinfunction "2_2") (pintype "input"))
      (node (ref "C39") (pin "2") (pinfunction "2_2") (pintype "input"))
      (node (ref "D6") (pin "1") (pinfunction "A_1") (pintype "input"))
      (node (ref "D8") (pin "1") (pinfunction "A_1") (pintype "input"))
      (node (ref "R66") (pin "2") (pinfunction "2_2") (pintype "input"))
      (node (ref "U11") (pin "4") (pinfunction "VCC-_4") (pintype "input"))
      (node (ref "U2") (pin "11") (pinfunction "VCC-_11") (pintype "input"))
      (node (ref "U3") (pin "7") (pinfunction "VEE_7") (pintype "input"))
    )
    (net (code "5") (name "-5V-D") (class "Default")
      (node (ref "C1") (pin "2") (pinfunction "2_2") (pintype "input"))
      (node (ref "C37") (pin "1") (pinfunction "1_1") (pintype "input"))
      (node (ref "C38") (pin "2") (pinfunction "2_2") (pintype "input"))
      (node (ref "C47") (pin "1") (pinfunction "1_1") (pintype "input"))
      (node (ref "C9") (pin "1") (pinfunction "1_1") (pintype "input"))
      (node (ref "D1") (pin "2") (pinfunction "A_2") (pintype "input"))
      (node (ref "Q2") (pin "3") (pinfunction "C_3") (pintype "input"))
      (node (ref "R12") (pin "1") (pinfunction "1_1") (pintype "input"))
      (node (ref "R24") (pin "1") (pinfunction "1_1") (pintype "input"))
      (node (ref "R66") (pin "1") (pinfunction "1_1") (pintype "input"))
      (node (ref "R76") (pin "2") (pinfunction "2_2") (pintype "input"))
      (node (ref "U1") (pin "11") (pinfunction "VCC-_11") (pintype "input"))
      (node (ref "U34") (pin "4") (pinfunction "GND_4") (pintype "input"))
      (node (ref "U8") (pin "7") (pinfunction "VEE_7") (pintype "input"))
    )
    (net (code "6") (name "/PA0_ADC") (class "Default")
      (node (ref "R62") (pin "2") (pinfunction "2_2") (pintype "input"))
      (node (ref "U6") (pin "6") (pinfunction "PA0_6") (pintype "bidirectional"))
    )
    (net (code "7") (name "/PA1_4053_11_SA_10X") (class "Default")
      (node (ref "U3") (pin "11") (pinfunction "SA_11") (pintype "input"))
      (node (ref "U6") (pin "7") (pinfunction "PA1_7") (pintype "bidirectional"))
    )
    (net (code "8") (name "/PA2_4053_10_SB_10X") (class "Default")
      (node (ref "U3") (pin "10") (pinfunction "SB_10") (pintype "input"))
      (node (ref "U6") (pin "8") (pinfunction "PA2_8") (pintype "bidirectional"))
    )
    (net (code "9") (name "/PA3_4053_9_SC_10X") (class "Default")
      (node (ref "U3") (pin "9") (pinfunction "SC_9") (pintype "input"))
      (node (ref "U6") (pin "9") (pinfunction "PA3_9") (pintype "bidirectional"))
    )
    (net (code "10") (name "/PA4_SPI1_NSS_HC595_12_RCK") (class "Default")
      (node (ref "R4") (pin "1") (pinfunction "1_1") (pintype "input"))
      (node (ref "U32") (pin "12") (pinfunction "RCK_12") (pintype "input"))
      (node (ref "U6") (pin "10") (pinfunction "PA4_10") (pintype "bidirectional"))
    )
    (net (code "11") (name "/PA5_SPI1_SCK_HC595_11_SCK") (class "Default")
      (node (ref "R25") (pin "1") (pinfunction "1_1") (pintype "input"))
      (node (ref "U32") (pin "11") (pinfunction "SCK_11") (pintype "input"))
      (node (ref "U6") (pin "11") (pinfunction "PA5_11") (pintype "bidirectional"))
    )
    (net (code "12") (name "/PA7_SPI1_MOSI_HC595_14_SER") (class "Default")
      (node (ref "R14") (pin "1") (pinfunction "1_1") (pintype "input"))
      (node (ref "U32") (pin "14") (pinfunction "SER_14") (pintype "input"))
      (node (ref "U6") (pin "13") (pinfunction "PA7_13") (pintype "bidirectional"))
    )
    (net (code "13") (name "/PA10_TIM1_SPWM") (class "Default")
      (node (ref "R22") (pin "2") (pinfunction "2_2") (pintype "input"))
      (node (ref "U6") (pin "18") (pinfunction "PA10_18") (pintype "bidirectional"))
    )
    (net (code "14") (name "/PB1_4053_DANG_WEI") (class "Default")
      (node (ref "U6") (pin "14") (pinfunction "PB1_14") (pintype "bidirectional"))
      (node (ref "U8") (pin "10") (pinfunction "SB_10") (pintype "input"))
      (node (ref "U8") (pin "11") (pinfunction "SA_11") (pintype "input"))
      (node (ref "U8") (pin "9") (pinfunction "SC_9") (pintype "input"))
    )
    (net (code "15") (name "GND") (class "Default")
      (node (ref "C1") (pin "1") (pinfunction "1_1") (pintype "input"))
      (node (ref "C12") (pin "2") (pinfunction "2_2") (pintype "input"))
      (node (ref "C13") (pin "1") (pinfunction "1_1") (pintype "input"))
      (node (ref "C14") (pin "2") (pinfunction "2_2") (pintype "input"))
      (node (ref "C15") (pin "2") (pinfunction "2_2") (pintype "input"))
      (node (ref "C16") (pin "2") (pinfunction "2_2") (pintype "input"))
      (node (ref "C17") (pin "1") (pinfunction "1_1") (pintype "input"))
      (node (ref "C18") (pin "1") (pinfunction "1_1") (pintype "input"))
      (node (ref "C19") (pin "2") (pinfunction "2_2") (pintype "input"))
      (node (ref "C2") (pin "1") (pinfunction "1_1") (pintype "input"))
      (node (ref "C20") (pin "1") (pinfunction "1_1") (pintype "input"))
      (node (ref "C21") (pin "1") (pinfunction "1_1") (pintype "input"))
      (node (ref "C22") (pin "1") (pinfunction "1_1") (pintype "input"))
      (node (ref "C23") (pin "1") (pinfunction "1_1") (pintype "input"))
      (node (ref "C25") (pin "1") (pinfunction "1_1") (pintype "input"))
      (node (ref "C34") (pin "1") (pinfunction "1_1") (pintype "input"))
      (node (ref "C35") (pin "2") (pinfunction "2_2") (pintype "input"))
      (node (ref "C37") (pin "2") (pinfunction "2_2") (pintype "input"))
      (node (ref "C38") (pin "1") (pinfunction "1_1") (pintype "input"))
      (node (ref "C39") (pin "1") (pinfunction "1_1") (pintype "input"))
      (node (ref "C4") (pin "1") (pinfunction "1_1") (pintype "input"))
      (node (ref "C40") (pin "1") (pinfunction "1_1") (pintype "input"))
      (node (ref "C41") (pin "1") (pinfunction "1_1") (pintype "input"))
      (node (ref "C42") (pin "2") (pinfunction "2_2") (pintype "input"))
      (node (ref "C43") (pin "1") (pinfunction "1_1") (pintype "input"))
      (node (ref "C46") (pin "2") (pinfunction "2_2") (pintype "input"))
      (node (ref "C48") (pin "1") (pinfunction "1_1") (pintype "input"))
      (node (ref "C5") (pin "1") (pinfunction "1_1") (pintype "input"))
      (node (ref "C50") (pin "1") (pinfunction "1_1") (pintype "input"))
      (node (ref "C6") (pin "1") (pinfunction "1_1") (pintype "input"))
      (node (ref "C7") (pin "1") (pinfunction "1_1") (pintype "input"))
      (node (ref "C8") (pin "1") (pinfunction "1_1") (pintype "input"))
      (node (ref "C9") (pin "2") (pinfunction "2_2") (pintype "input"))
      (node (ref "D12") (pin "1") (pinfunction "1_1") (pintype "input"))
      (node (ref "H5") (pin "3") (pinfunction "3_3") (pintype "input"))
      (node (ref "L3") (pin "1") (pinfunction "1_1") (pintype "input"))
      (node (ref "LC1") (pin "1") (pinfunction "1_1") (pintype "unspecified"))
      (node (ref "LCD1") (pin "1") (pinfunction "VSS_1") (pintype "input"))
      (node (ref "LCD1") (pin "5") (pinfunction "RW_5") (pintype "input"))
      (node (ref "LDO1") (pin "1") (pinfunction "GND_1") (pintype "input"))
      (node (ref "R1") (pin "1") (pinfunction "1_1") (pintype "input"))
      (node (ref "R15") (pin "1") (pinfunction "1_1") (pintype "input"))
      (node (ref "R18") (pin "1") (pinfunction "1_1") (pintype "input"))
      (node (ref "R2") (pin "1") (pinfunction "1_1") (pintype "input"))
      (node (ref "R28") (pin "1") (pinfunction "1_1") (pintype "input"))
      (node (ref "R29") (pin "1") (pinfunction "1_1") (pintype "input"))
      (node (ref "R33") (pin "2") (pinfunction "2_2") (pintype "input"))
      (node (ref "R35") (pin "2") (pinfunction "2_2") (pintype "input"))
      (node (ref "R39") (pin "1") (pinfunction "1_1") (pintype "input"))
      (node (ref "R41") (pin "1") (pinfunction "1_1") (pintype "input"))
      (node (ref "R45") (pin "1") (pinfunction "1_1") (pintype "input"))
      (node (ref "R48") (pin "1") (pinfunction "1_1") (pintype "input"))
      (node (ref "R51") (pin "1") (pinfunction "1_1") (pintype "input"))
      (node (ref "R56") (pin "1") (pinfunction "1_1") (pintype "input"))
      (node (ref "R58") (pin "1") (pinfunction "1_1") (pintype "input"))
      (node (ref "R61") (pin "1") (pinfunction "1_1") (pintype "input"))
      (node (ref "R63") (pin "1") (pinfunction "1_1") (pintype "input"))
      (node (ref "R75") (pin "1") (pinfunction "1_1") (pintype "input"))
      (node (ref "R77") (pin "1") (pinfunction "1_1") (pintype "input"))
      (node (ref "R78") (pin "1") (pinfunction "1_1") (pintype "input"))
      (node (ref "R79") (pin "1") (pinfunction "1_1") (pintype "input"))
      (node (ref "R80") (pin "1") (pinfunction "1_1") (pintype "input"))
      (node (ref "R83") (pin "2") (pinfunction "2_2") (pintype "input"))
      (node (ref "SW1") (pin "3") (pinfunction "3_3") (pintype "input"))
      (node (ref "SW1") (pin "4") (pinfunction "4_4") (pintype "input"))
      (node (ref "SW2") (pin "3") (pinfunction "3_3") (pintype "input"))
      (node (ref "SW2") (pin "4") (pinfunction "4_4") (pintype "input"))
      (node (ref "U3") (pin "6") (pinfunction "E#_6") (pintype "input"))
      (node (ref "U3") (pin "8") (pinfunction "VSS_8") (pintype "input"))
      (node (ref "U32") (pin "13") (pinfunction "NC_13") (pintype "input"))
      (node (ref "U32") (pin "8") (pinfunction "GND_8") (pintype "input"))
      (node (ref "U33") (pin "2") (pinfunction "SE_2") (pintype "input"))
      (node (ref "U33") (pin "4") (pinfunction "GND_4") (pintype "input"))
      (node (ref "U35") (pin "1") (pinfunction "TEMP_1") (pintype "input"))
      (node (ref "U35") (pin "3") (pinfunction "GND_3") (pintype "input"))
      (node (ref "U37") (pin "2") (pinfunction "S_2") (pintype "input"))
      (node (ref "U6") (pin "15") (pinfunction "VSS_15") (pintype "input"))
      (node (ref "U8") (pin "6") (pinfunction "E#_6") (pintype "input"))
      (node (ref "U8") (pin "8") (pinfunction "VSS_8") (pintype "input"))
      (node (ref "USB1") (pin "1") (pinfunction "GND_1") (pintype "input"))
      (node (ref "USB1") (pin "12") (pinfunction "GND_12") (pintype "input"))
      (node (ref "USB1") (pin "13") (pinfunction "SHELL_13") (pintype "input"))
      (node (ref "USB1") (pin "14") (pinfunction "SHELL_14") (pintype "input"))
    )
    (net (code "16") (name "Net-(C3-Pad2)") (class "Default")
      (node (ref "C3") (pin "2") (pinfunction "2_2") (pintype "input"))
      (node (ref "C7") (pin "2") (pinfunction "2_2") (pintype "input"))
      (node (ref "R19") (pin "1") (pinfunction "1_1") (pintype "input"))
    )
    (net (code "17") (name "Net-(C4-Pad2)") (class "Default")
      (node (ref "C4") (pin "2") (pinfunction "2_2") (pintype "input"))
      (node (ref "R21") (pin "2") (pinfunction "2_2") (pintype "input"))
      (node (ref "R22") (pin "1") (pinfunction "1_1") (pintype "input"))
    )
    (net (code "18") (name "Net-(C5-Pad2)") (class "Default")
      (node (ref "C5") (pin "2") (pinfunction "2_2") (pintype "input"))
      (node (ref "R20") (pin "2") (pinfunction "2_2") (pintype "input"))
      (node (ref "R21") (pin "1") (pinfunction "1_1") (pintype "input"))
    )
    (net (code "19") (name "Net-(C6-Pad2)") (class "Default")
      (node (ref "C6") (pin "2") (pinfunction "2_2") (pintype "input"))
      (node (ref "R19") (pin "2") (pinfunction "2_2") (pintype "input"))
      (node (ref "R20") (pin "1") (pinfunction "1_1") (pintype "input"))
    )
    (net (code "20") (name "Net-(C24-Pad1)") (class "Default")
      (node (ref "C24") (pin "1") (pinfunction "1_1") (pintype "input"))
      (node (ref "C25") (pin "2") (pinfunction "2_2") (pintype "input"))
      (node (ref "R54") (pin "2") (pinfunction "2_2") (pintype "input"))
      (node (ref "R55") (pin "1") (pinfunction "1_1") (pintype "input"))
      (node (ref "R56") (pin "2") (pinfunction "2_2") (pintype "input"))
      (node (ref "R57") (pin "2") (pinfunction "2_2") (pintype "input"))
    )
    (net (code "21") (name "Net-(C44-Pad1)") (class "Default")
      (node (ref "C44") (pin "1") (pinfunction "1_1") (pintype "input"))
      (node (ref "R28") (pin "2") (pinfunction "2_2") (pintype "input"))
      (node (ref "R31") (pin "1") (pinfunction "1_1") (pintype "input"))
    )
    (net (code "22") (name "Net-(C44-Pad2)") (class "Default")
      (node (ref "C44") (pin "2") (pinfunction "2_2") (pintype "input"))
      (node (ref "LP1") (pin "1") (pinfunction "1_1") (pintype "unspecified"))
    )
    (net (code "23") (name "Net-(C45-Pad1)") (class "Default")
      (node (ref "C45") (pin "1") (pinfunction "1_1") (pintype "input"))
      (node (ref "R29") (pin "2") (pinfunction "2_2") (pintype "input"))
      (node (ref "R30") (pin "1") (pinfunction "1_1") (pintype "input"))
    )
    (net (code "24") (name "Net-(C45-Pad2)") (class "Default")
      (node (ref "C45") (pin "2") (pinfunction "2_2") (pintype "input"))
      (node (ref "HP1") (pin "1") (pinfunction "1_1") (pintype "unspecified"))
    )
    (net (code "25") (name "Net-(D1-K)") (class "Default")
      (node (ref "D1") (pin "1") (pinfunction "K_1") (pintype "input"))
      (node (ref "L3") (pin "2") (pinfunction "2_2") (pintype "input"))
      (node (ref "U34") (pin "2") (pinfunction "SE_2") (pintype "input"))
    )
    (net (code "26") (name "Net-(D2-A)") (class "Default")
      (node (ref "D2") (pin "1") (pinfunction "A_1") (pintype "input"))
      (node (ref "Q4") (pin "1") (pinfunction "B_1") (pintype "input"))
      (node (ref "R11") (pin "1") (pinfunction "1_1") (pintype "input"))
    )
    (net (code "27") (name "Net-(D2-C)") (class "Default")
      (node (ref "D2") (pin "2") (pinfunction "C_2") (pintype "input"))
      (node (ref "D3") (pin "1") (pinfunction "A_1") (pintype "input"))
      (node (ref "U1") (pin "7") (pinfunction "OUT2_7") (pintype "input"))
    )
    (net (code "28") (name "Net-(D3-C)") (class "Default")
      (node (ref "D3") (pin "2") (pinfunction "C_2") (pintype "input"))
      (node (ref "Q2") (pin "1") (pinfunction "B_1") (pintype "input"))
      (node (ref "R12") (pin "2") (pinfunction "2_2") (pintype "input"))
    )
    (net (code "29") (name "Net-(D4-A)") (class "Default")
      (node (ref "C10") (pin "2") (pinfunction "2_2") (pintype "input"))
      (node (ref "C11") (pin "2") (pinfunction "2_2") (pintype "input"))
      (node (ref "D4") (pin "2") (pinfunction "A_2") (pintype "input"))
      (node (ref "D5") (pin "2") (pinfunction "A_2") (pintype "input"))
    )
    (net (code "30") (name "Net-(D4-K)") (class "Default")
      (node (ref "C10") (pin "1") (pinfunction "1_1") (pintype "input"))
      (node (ref "D12") (pin "2") (pinfunction "2_2") (pintype "input"))
      (node (ref "D4") (pin "1") (pinfunction "K_1") (pintype "input"))
      (node (ref "Q7") (pin "2") (pinfunction "S_2") (pintype "input"))
      (node (ref "R6") (pin "1") (pinfunction "1_1") (pintype "input"))
      (node (ref "R71") (pin "1") (pinfunction "1_1") (pintype "input"))
    )
    (net (code "31") (name "Net-(D5-K)") (class "Default")
      (node (ref "C11") (pin "1") (pinfunction "1_1") (pintype "input"))
      (node (ref "D5") (pin "1") (pinfunction "K_1") (pintype "input"))
      (node (ref "HC1") (pin "1") (pinfunction "1_1") (pintype "unspecified"))
    )
    (net (code "32") (name "Net-(D6-C)") (class "Default")
      (node (ref "D6") (pin "2") (pinfunction "C_2") (pintype "input"))
      (node (ref "D7") (pin "1") (pinfunction "A_1") (pintype "input"))
      (node (ref "R30") (pin "2") (pinfunction "2_2") (pintype "input"))
      (node (ref "U2") (pin "3") (pinfunction "POS1_3") (pintype "input"))
    )
    (net (code "33") (name "Net-(D8-C)") (class "Default")
      (node (ref "D8") (pin "2") (pinfunction "C_2") (pintype "input"))
      (node (ref "D9") (pin "1") (pinfunction "A_1") (pintype "input"))
      (node (ref "R31") (pin "2") (pinfunction "2_2") (pintype "input"))
      (node (ref "U2") (pin "12") (pinfunction "POS4_12") (pintype "input"))
    )
    (net (code "34") (name "Net-(D13-A)") (class "Default")
      (node (ref "D13") (pin "2") (pinfunction "A_2") (pintype "input"))
      (node (ref "L2") (pin "2") (pinfunction "2_2") (pintype "input"))
      (node (ref "U33") (pin "1") (pinfunction "SC_1") (pintype "input"))
    )
    (net (code "35") (name "Net-(LCD1-DB4)") (class "Default")
      (node (ref "LCD1") (pin "11") (pinfunction "DB4_11") (pintype "input"))
      (node (ref "U32") (pin "2") (pinfunction "Q2_2") (pintype "input"))
    )
    (net (code "36") (name "Net-(LCD1-DB5)") (class "Default")
      (node (ref "LCD1") (pin "12") (pinfunction "DB5_12") (pintype "input"))
      (node (ref "U32") (pin "3") (pinfunction "Q3_3") (pintype "input"))
    )
    (net (code "37") (name "Net-(LCD1-DB6)") (class "Default")
      (node (ref "LCD1") (pin "13") (pinfunction "DB6_13") (pintype "input"))
      (node (ref "U32") (pin "4") (pinfunction "Q4_4") (pintype "input"))
    )
    (net (code "38") (name "Net-(LCD1-DB7)") (class "Default")
      (node (ref "LCD1") (pin "14") (pinfunction "DB7_14") (pintype "input"))
      (node (ref "U32") (pin "5") (pinfunction "Q5_5") (pintype "input"))
    )
    (net (code "39") (name "Net-(LCD1-E)") (class "Default")
      (node (ref "LCD1") (pin "6") (pinfunction "E_6") (pintype "input"))
      (node (ref "U32") (pin "1") (pinfunction "Q1_1") (pintype "input"))
    )
    (net (code "40") (name "Net-(LCD1-K)") (class "Default")
      (node (ref "LCD1") (pin "16") (pinfunction "K_16") (pintype "input"))
      (node (ref "R33") (pin "1") (pinfunction "1_1") (pintype "input"))
    )
    (net (code "41") (name "Net-(LCD1-RS)") (class "Default")
      (node (ref "LCD1") (pin "4") (pinfunction "RS_4") (pintype "input"))
      (node (ref "U32") (pin "15") (pinfunction "Q0_15") (pintype "input"))
    )
    (net (code "42") (name "Net-(LCD1-V0)") (class "Default")
      (node (ref "LCD1") (pin "3") (pinfunction "V0_3") (pintype "input"))
      (node (ref "R34") (pin "2") (pinfunction "2_2") (pintype "input"))
    )
    (net (code "43") (name "Net-(LDO1-VDD)") (class "Default")
      (node (ref "C12") (pin "1") (pinfunction "1_1") (pintype "input"))
      (node (ref "C48") (pin "2") (pinfunction "2_2") (pintype "input"))
      (node (ref "LDO1") (pin "3") (pinfunction "VDD_3") (pintype "input"))
      (node (ref "R26") (pin "2") (pinfunction "2_2") (pintype "input"))
      (node (ref "R72") (pin "2") (pinfunction "2_2") (pintype "input"))
      (node (ref "SW3") (pin "2") (pinfunction "2_2") (pintype "input"))
      (node (ref "SW3") (pin "3") (pinfunction "3_3") (pintype "input"))
      (node (ref "U33") (pin "6") (pinfunction "VCC_6") (pintype "input"))
      (node (ref "U34") (pin "6") (pinfunction "VCC_6") (pintype "input"))
    )
    (net (code "44") (name "Net-(LED1-A)") (class "Default")
      (node (ref "LED1") (pin "2") (pinfunction "A_2") (pintype "input"))
      (node (ref "R81") (pin "2") (pinfunction "2_2") (pintype "input"))
    )
    (net (code "45") (name "Net-(LED1-C)") (class "Default")
      (node (ref "C50") (pin "2") (pinfunction "2_2") (pintype "input"))
      (node (ref "LED1") (pin "1") (pinfunction "C_1") (pintype "input"))
      (node (ref "LED2") (pin "1") (pinfunction "C_1") (pintype "input"))
      (node (ref "U35") (pin "4") (pinfunction "Vcc_4") (pintype "input"))
      (node (ref "U35") (pin "8") (pinfunction "CE_8") (pintype "input"))
      (node (ref "USB1") (pin "11") (pinfunction "VBUS_11") (pintype "input"))
      (node (ref "USB1") (pin "2") (pinfunction "VBUS_2") (pintype "input"))
    )
    (net (code "46") (name "Net-(LED2-A)") (class "Default")
      (node (ref "LED2") (pin "2") (pinfunction "A_2") (pintype "input"))
      (node (ref "R82") (pin "2") (pinfunction "2_2") (pintype "input"))
    )
    (net (code "47") (name "Net-(Q2-E)") (class "Default")
      (node (ref "Q2") (pin "2") (pinfunction "E_2") (pintype "input"))
      (node (ref "R9") (pin "1") (pinfunction "1_1") (pintype "input"))
    )
    (net (code "48") (name "Net-(Q4-E)") (class "Default")
      (node (ref "Q4") (pin "2") (pinfunction "E_2") (pintype "input"))
      (node (ref "R10") (pin "2") (pinfunction "2_2") (pintype "input"))
    )
    (net (code "49") (name "Net-(Q6-D)") (class "Default")
      (node (ref "Q6") (pin "3") (pinfunction "D_3") (pintype "input"))
      (node (ref "Q7") (pin "3") (pinfunction "D_3") (pintype "input"))
    )
    (net (code "50") (name "Net-(Q6-G)") (class "Default")
      (node (ref "Q6") (pin "1") (pinfunction "G_1") (pintype "input"))
      (node (ref "Q7") (pin "1") (pinfunction "G_1") (pintype "input"))
      (node (ref "U8") (pin "14") (pinfunction "ZA_14") (pintype "input"))
    )
    (net (code "51") (name "Net-(Q6-S)") (class "Default")
      (node (ref "Q6") (pin "2") (pinfunction "S_2") (pintype "input"))
      (node (ref "R5") (pin "1") (pinfunction "1_1") (pintype "input"))
      (node (ref "R69") (pin "1") (pinfunction "1_1") (pintype "input"))
      (node (ref "R71") (pin "2") (pinfunction "2_2") (pintype "input"))
    )
    (net (code "52") (name "Net-(R1-Pad2)") (class "Default")
      (node (ref "R1") (pin "2") (pinfunction "2_2") (pintype "input"))
      (node (ref "R2") (pin "2") (pinfunction "2_2") (pintype "input"))
      (node (ref "R34") (pin "1") (pinfunction "1_1") (pintype "input"))
    )
    (net (code "53") (name "Net-(R10-Pad1)") (class "Default")
      (node (ref "R10") (pin "1") (pinfunction "1_1") (pintype "input"))
      (node (ref "R3") (pin "1") (pinfunction "1_1") (pintype "input"))
      (node (ref "R69") (pin "2") (pinfunction "2_2") (pintype "input"))
      (node (ref "R9") (pin "2") (pinfunction "2_2") (pintype "input"))
    )
    (net (code "54") (name "Net-(U1-NEG1)") (class "Default")
      (node (ref "R13") (pin "2") (pinfunction "2_2") (pintype "input"))
      (node (ref "U1") (pin "1") (pinfunction "OUT1_1") (pintype "input"))
      (node (ref "U1") (pin "2") (pinfunction "NEG1_2") (pintype "input"))
    )
    (net (code "55") (name "Net-(U1-NEG2)") (class "Default")
      (node (ref "R13") (pin "1") (pinfunction "1_1") (pintype "input"))
      (node (ref "R17") (pin "2") (pinfunction "2_2") (pintype "input"))
      (node (ref "U1") (pin "6") (pinfunction "NEG2_6") (pintype "input"))
    )
    (net (code "56") (name "Net-(U1-NEG3)") (class "Default")
      (node (ref "R17") (pin "1") (pinfunction "1_1") (pintype "input"))
      (node (ref "U1") (pin "8") (pinfunction "OUT3_8") (pintype "input"))
      (node (ref "U1") (pin "9") (pinfunction "NEG3_9") (pintype "input"))
    )
    (net (code "57") (name "Net-(U1-NEG4)") (class "Default")
      (node (ref "R16") (pin "2") (pinfunction "2_2") (pintype "input"))
      (node (ref "U1") (pin "13") (pinfunction "NEG4_13") (pintype "input"))
      (node (ref "U1") (pin "14") (pinfunction "OUT4_14") (pintype "input"))
    )
    (net (code "58") (name "Net-(U1-POS1)") (class "Default")
      (node (ref "U1") (pin "3") (pinfunction "POS1_3") (pintype "input"))
      (node (ref "U8") (pin "4") (pinfunction "ZC_4") (pintype "input"))
    )
    (net (code "59") (name "Net-(U1-POS2)") (class "Default")
      (node (ref "R15") (pin "2") (pinfunction "2_2") (pintype "input"))
      (node (ref "R16") (pin "1") (pinfunction "1_1") (pintype "input"))
      (node (ref "U1") (pin "5") (pinfunction "POS2_5") (pintype "input"))
    )
    (net (code "60") (name "Net-(U1-POS3)") (class "Default")
      (node (ref "C3") (pin "1") (pinfunction "1_1") (pintype "input"))
      (node (ref "R18") (pin "2") (pinfunction "2_2") (pintype "input"))
      (node (ref "U1") (pin "10") (pinfunction "POS3_10") (pintype "input"))
    )
    (net (code "61") (name "Net-(U1-POS4)") (class "Default")
      (node (ref "U1") (pin "12") (pinfunction "POS4_12") (pintype "input"))
      (node (ref "U8") (pin "15") (pinfunction "ZB_15") (pintype "input"))
    )
    (net (code "62") (name "Net-(U2-NEG1)") (class "Default")
      (node (ref "R42") (pin "1") (pinfunction "1_1") (pintype "input"))
      (node (ref "U2") (pin "1") (pinfunction "OUT1_1") (pintype "input"))
      (node (ref "U2") (pin "2") (pinfunction "NEG1_2") (pintype "input"))
    )
    (net (code "63") (name "Net-(U2-NEG2)") (class "Default")
      (node (ref "C30") (pin "1") (pinfunction "1_1") (pintype "input"))
      (node (ref "R36") (pin "2") (pinfunction "2_2") (pintype "input"))
      (node (ref "R38") (pin "1") (pinfunction "1_1") (pintype "input"))
      (node (ref "R39") (pin "2") (pinfunction "2_2") (pintype "input"))
      (node (ref "U2") (pin "6") (pinfunction "NEG2_6") (pintype "input"))
    )
    (net (code "64") (name "Net-(U2-NEG3)") (class "Default")
      (node (ref "R37") (pin "1") (pinfunction "1_1") (pintype "input"))
      (node (ref "R42") (pin "2") (pinfunction "2_2") (pintype "input"))
      (node (ref "U2") (pin "9") (pinfunction "NEG3_9") (pintype "input"))
    )
    (net (code "65") (name "Net-(U2-NEG4)") (class "Default")
      (node (ref "R40") (pin "2") (pinfunction "2_2") (pintype "input"))
      (node (ref "U2") (pin "13") (pinfunction "NEG4_13") (pintype "input"))
      (node (ref "U2") (pin "14") (pinfunction "OUT4_14") (pintype "input"))
    )
    (net (code "66") (name "Net-(U2-OUT2)") (class "Default")
      (node (ref "C30") (pin "2") (pinfunction "2_2") (pintype "input"))
      (node (ref "R36") (pin "1") (pinfunction "1_1") (pintype "input"))
      (node (ref "R38") (pin "2") (pinfunction "2_2") (pintype "input"))
      (node (ref "R43") (pin "2") (pinfunction "2_2") (pintype "input"))
      (node (ref "R44") (pin "2") (pinfunction "2_2") (pintype "input"))
      (node (ref "U2") (pin "7") (pinfunction "OUT2_7") (pintype "input"))
      (node (ref "U3") (pin "1") (pinfunction "Y1B_1") (pintype "input"))
    )
    (net (code "67") (name "Net-(U2-OUT3)") (class "Default")
      (node (ref "R37") (pin "2") (pinfunction "2_2") (pintype "input"))
      (node (ref "R46") (pin "2") (pinfunction "2_2") (pintype "input"))
      (node (ref "R47") (pin "2") (pinfunction "2_2") (pintype "input"))
      (node (ref "U2") (pin "8") (pinfunction "OUT3_8") (pintype "input"))
      (node (ref "U3") (pin "3") (pinfunction "Y1C_3") (pintype "input"))
    )
    (net (code "68") (name "Net-(U2-POS2)") (class "Default")
      (node (ref "C31") (pin "2") (pinfunction "2_2") (pintype "input"))
      (node (ref "R63") (pin "2") (pinfunction "2_2") (pintype "input"))
      (node (ref "U2") (pin "5") (pinfunction "POS2_5") (pintype "input"))
    )
    (net (code "69") (name "Net-(U2-POS3)") (class "Default")
      (node (ref "R40") (pin "1") (pinfunction "1_1") (pintype "input"))
      (node (ref "R41") (pin "2") (pinfunction "2_2") (pintype "input"))
      (node (ref "U2") (pin "10") (pinfunction "POS3_10") (pintype "input"))
    )
    (net (code "70") (name "Net-(U3-Y0A)") (class "Default")
      (node (ref "R49") (pin "1") (pinfunction "1_1") (pintype "input"))
      (node (ref "R50") (pin "1") (pinfunction "1_1") (pintype "input"))
      (node (ref "R51") (pin "2") (pinfunction "2_2") (pintype "input"))
      (node (ref "U3") (pin "12") (pinfunction "Y0A_12") (pintype "input"))
    )
    (net (code "71") (name "Net-(U3-Y0B)") (class "Default")
      (node (ref "R43") (pin "1") (pinfunction "1_1") (pintype "input"))
      (node (ref "R44") (pin "1") (pinfunction "1_1") (pintype "input"))
      (node (ref "R45") (pin "2") (pinfunction "2_2") (pintype "input"))
      (node (ref "U3") (pin "2") (pinfunction "Y0B_2") (pintype "input"))
    )
    (net (code "72") (name "Net-(U3-Y0C)") (class "Default")
      (node (ref "R46") (pin "1") (pinfunction "1_1") (pintype "input"))
      (node (ref "R47") (pin "1") (pinfunction "1_1") (pintype "input"))
      (node (ref "R48") (pin "2") (pinfunction "2_2") (pintype "input"))
      (node (ref "U3") (pin "5") (pinfunction "Y0C_5") (pintype "input"))
    )
    (net (code "73") (name "Net-(U3-ZA)") (class "Default")
      (node (ref "C26") (pin "1") (pinfunction "1_1") (pintype "input"))
      (node (ref "U3") (pin "14") (pinfunction "ZA_14") (pintype "input"))
    )
    (net (code "74") (name "Net-(U3-ZB)") (class "Default")
      (node (ref "C27") (pin "1") (pinfunction "1_1") (pintype "input"))
      (node (ref "U3") (pin "15") (pinfunction "ZB_15") (pintype "input"))
    )
    (net (code "75") (name "Net-(U3-ZC)") (class "Default")
      (node (ref "C31") (pin "1") (pinfunction "1_1") (pintype "input"))
      (node (ref "U3") (pin "4") (pinfunction "ZC_4") (pintype "input"))
    )
    (net (code "76") (name "Net-(U6-BOOT0)") (class "Default")
      (node (ref "R35") (pin "1") (pinfunction "1_1") (pintype "input"))
      (node (ref "U6") (pin "1") (pinfunction "BOOT0_1") (pintype "input"))
    )
    (net (code "77") (name "Net-(U6-NRST)") (class "Default")
      (node (ref "C14") (pin "1") (pinfunction "1_1") (pintype "input"))
      (node (ref "U6") (pin "4") (pinfunction "NRST_4") (pintype "bidirectional"))
    )
    (net (code "78") (name "Net-(U6-PA6)") (class "Default")
      (node (ref "SW1") (pin "1") (pinfunction "1_1") (pintype "input"))
      (node (ref "SW1") (pin "2") (pinfunction "2_2") (pintype "input"))
      (node (ref "U6") (pin "12") (pinfunction "PA6_12") (pintype "bidirectional"))
    )
    (net (code "79") (name "Net-(U6-PA9)") (class "Default")
      (node (ref "SW2") (pin "1") (pinfunction "1_1") (pintype "input"))
      (node (ref "SW2") (pin "2") (pinfunction "2_2") (pintype "input"))
      (node (ref "U6") (pin "17") (pinfunction "PA9_17") (pintype "bidirectional"))
    )
    (net (code "80") (name "Net-(U6-PA13(SWDIO))") (class "Default")
      (node (ref "H5") (pin "2") (pinfunction "2_2") (pintype "input"))
      (node (ref "U6") (pin "19") (pinfunction "PA13(SWDIO)_19") (pintype "bidirectional"))
    )
    (net (code "81") (name "Net-(U6-PA14(SWCLK))") (class "Default")
      (node (ref "H5") (pin "1") (pinfunction "1_1") (pintype "input"))
      (node (ref "U6") (pin "20") (pinfunction "PA14(SWCLK)_20") (pintype "bidirectional"))
    )
    (net (code "82") (name "Net-(U6-PF0-OSC_IN(PF0))") (class "Default")
      (node (ref "C15") (pin "1") (pinfunction "1_1") (pintype "input"))
      (node (ref "U6") (pin "2") (pinfunction "PF0-OSC_IN(PF0)_2") (pintype "bidirectional"))
      (node (ref "X1") (pin "1") (pinfunction "OSC1_1") (pintype "input"))
    )
    (net (code "83") (name "Net-(U6-PF1-OSC_OUT(PF1))") (class "Default")
      (node (ref "C16") (pin "1") (pinfunction "1_1") (pintype "input"))
      (node (ref "U6") (pin "3") (pinfunction "PF1-OSC_OUT(PF1)_3") (pintype "bidirectional"))
      (node (ref "X1") (pin "2") (pinfunction "OSC2_2") (pintype "input"))
    )
    (net (code "84") (name "Net-(U6-VDDA)") (class "Default")
      (node (ref "C17") (pin "2") (pinfunction "2_2") (pintype "input"))
      (node (ref "L1") (pin "1") (pinfunction "1_1") (pintype "input"))
      (node (ref "U6") (pin "5") (pinfunction "VDDA_5") (pintype "input"))
    )
    (net (code "85") (name "Net-(U8-Y0A)") (class "Default")
      (node (ref "R23") (pin "2") (pinfunction "2_2") (pintype "input"))
      (node (ref "U8") (pin "12") (pinfunction "Y0A_12") (pintype "input"))
    )
    (net (code "86") (name "Net-(U8-Y0B)") (class "Default")
      (node (ref "R5") (pin "2") (pinfunction "2_2") (pintype "input"))
      (node (ref "U8") (pin "2") (pinfunction "Y0B_2") (pintype "input"))
      (node (ref "U8") (pin "3") (pinfunction "Y1C_3") (pintype "input"))
    )
    (net (code "87") (name "Net-(U8-Y0C)") (class "Default")
      (node (ref "R3") (pin "2") (pinfunction "2_2") (pintype "input"))
      (node (ref "U8") (pin "5") (pinfunction "Y0C_5") (pintype "input"))
    )
    (net (code "88") (name "Net-(U8-Y1A)") (class "Default")
      (node (ref "R24") (pin "2") (pinfunction "2_2") (pintype "input"))
      (node (ref "U8") (pin "13") (pinfunction "Y1A_13") (pintype "input"))
    )
    (net (code "89") (name "Net-(U8-Y1B)") (class "Default")
      (node (ref "R6") (pin "2") (pinfunction "2_2") (pintype "input"))
      (node (ref "U8") (pin "1") (pinfunction "Y1B_1") (pintype "input"))
    )
    (net (code "90") (name "Net-(U11A-IN1+)") (class "Default")
      (node (ref "C26") (pin "2") (pinfunction "2_2") (pintype "input"))
      (node (ref "R57") (pin "1") (pinfunction "1_1") (pintype "input"))
      (node (ref "U11") (pin "3") (pinfunction "IN1+_3") (pintype "input"))
    )
    (net (code "91") (name "Net-(U11A-IN1-)") (class "Default")
      (node (ref "C28") (pin "1") (pinfunction "1_1") (pintype "input"))
      (node (ref "R52") (pin "1") (pinfunction "1_1") (pintype "input"))
      (node (ref "R53") (pin "2") (pinfunction "2_2") (pintype "input"))
      (node (ref "R54") (pin "1") (pinfunction "1_1") (pintype "input"))
      (node (ref "U11") (pin "2") (pinfunction "IN1-_2") (pintype "input"))
    )
    (net (code "92") (name "Net-(U11A-OUT1)") (class "Default")
      (node (ref "C28") (pin "2") (pinfunction "2_2") (pintype "input"))
      (node (ref "R52") (pin "2") (pinfunction "2_2") (pintype "input"))
      (node (ref "R53") (pin "1") (pinfunction "1_1") (pintype "input"))
      (node (ref "R62") (pin "1") (pinfunction "1_1") (pintype "input"))
      (node (ref "U11") (pin "1") (pinfunction "OUT1_1") (pintype "output"))
    )
    (net (code "93") (name "Net-(U11B-IN2+)") (class "Default")
      (node (ref "C27") (pin "2") (pinfunction "2_2") (pintype "input"))
      (node (ref "R58") (pin "2") (pinfunction "2_2") (pintype "input"))
      (node (ref "U11") (pin "5") (pinfunction "IN2+_5") (pintype "input"))
    )
    (net (code "94") (name "Net-(U11B-IN2-)") (class "Default")
      (node (ref "C29") (pin "1") (pinfunction "1_1") (pintype "input"))
      (node (ref "R59") (pin "1") (pinfunction "1_1") (pintype "input"))
      (node (ref "R60") (pin "2") (pinfunction "2_2") (pintype "input"))
      (node (ref "R61") (pin "2") (pinfunction "2_2") (pintype "input"))
      (node (ref "U11") (pin "6") (pinfunction "IN2-_6") (pintype "input"))
    )
    (net (code "95") (name "Net-(U11B-OUT2)") (class "Default")
      (node (ref "C29") (pin "2") (pinfunction "2_2") (pintype "input"))
      (node (ref "R49") (pin "2") (pinfunction "2_2") (pintype "input"))
      (node (ref "R50") (pin "2") (pinfunction "2_2") (pintype "input"))
      (node (ref "R59") (pin "2") (pinfunction "2_2") (pintype "input"))
      (node (ref "R60") (pin "1") (pinfunction "1_1") (pintype "input"))
      (node (ref "U11") (pin "7") (pinfunction "OUT2_7") (pintype "output"))
      (node (ref "U3") (pin "13") (pinfunction "Y1A_13") (pintype "input"))
    )
    (net (code "96") (name "Net-(U33-CT)") (class "Default")
      (node (ref "C46") (pin "1") (pinfunction "1_1") (pintype "input"))
      (node (ref "U33") (pin "3") (pinfunction "CT_3") (pintype "input"))
    )
    (net (code "97") (name "Net-(U33-DC)") (class "Default")
      (node (ref "R73") (pin "1") (pinfunction "1_1") (pintype "input"))
      (node (ref "U33") (pin "8") (pinfunction "DC_8") (pintype "input"))
    )
    (net (code "98") (name "Net-(U33-FB)") (class "Default")
      (node (ref "R74") (pin "1") (pinfunction "1_1") (pintype "input"))
      (node (ref "R75") (pin "2") (pinfunction "2_2") (pintype "input"))
      (node (ref "U33") (pin "5") (pinfunction "FB_5") (pintype "input"))
    )
    (net (code "99") (name "Net-(U33-IPK)") (class "Default")
      (node (ref "L2") (pin "1") (pinfunction "1_1") (pintype "input"))
      (node (ref "R72") (pin "1") (pinfunction "1_1") (pintype "input"))
      (node (ref "R73") (pin "2") (pinfunction "2_2") (pintype "input"))
      (node (ref "U33") (pin "7") (pinfunction "IPK_7") (pintype "input"))
    )
    (net (code "100") (name "Net-(U34-CT)") (class "Default")
      (node (ref "C47") (pin "2") (pinfunction "2_2") (pintype "input"))
      (node (ref "U34") (pin "3") (pinfunction "CT_3") (pintype "input"))
    )
    (net (code "101") (name "Net-(U34-DC)") (class "Default")
      (node (ref "R26") (pin "1") (pinfunction "1_1") (pintype "input"))
      (node (ref "U34") (pin "1") (pinfunction "SC_1") (pintype "input"))
      (node (ref "U34") (pin "7") (pinfunction "IPK_7") (pintype "input"))
      (node (ref "U34") (pin "8") (pinfunction "DC_8") (pintype "input"))
    )
    (net (code "102") (name "Net-(U34-FB)") (class "Default")
      (node (ref "R76") (pin "1") (pinfunction "1_1") (pintype "input"))
      (node (ref "R77") (pin "2") (pinfunction "2_2") (pintype "input"))
      (node (ref "U34") (pin "5") (pinfunction "FB_5") (pintype "input"))
    )
    (net (code "103") (name "Net-(U35-BAT)") (class "Default")
      (node (ref "C13") (pin "2") (pinfunction "2_2") (pintype "input"))
      (node (ref "H6") (pin "1") (pinfunction "1_1") (pintype "unspecified"))
      (node (ref "R84") (pin "1") (pinfunction "1_1") (pintype "input"))
      (node (ref "SW3") (pin "1") (pinfunction "1_1") (pintype "input"))
      (node (ref "U35") (pin "5") (pinfunction "BAT_5") (pintype "input"))
    )
    (net (code "104") (name "Net-(U35-CHRG#)") (class "Default")
      (node (ref "R81") (pin "1") (pinfunction "1_1") (pintype "input"))
      (node (ref "U35") (pin "7") (pinfunction "CHRG#_7") (pintype "input"))
    )
    (net (code "105") (name "Net-(U35-PROG)") (class "Default")
      (node (ref "R80") (pin "2") (pinfunction "2_2") (pintype "input"))
      (node (ref "U35") (pin "2") (pinfunction "PROG_2") (pintype "input"))
    )
    (net (code "106") (name "Net-(U35-STDBY#)") (class "Default")
      (node (ref "R82") (pin "1") (pinfunction "1_1") (pintype "input"))
      (node (ref "U35") (pin "6") (pinfunction "STDBY#_6") (pintype "input"))
    )
    (net (code "107") (name "Net-(U36-CS)") (class "Default")
      (node (ref "R83") (pin "1") (pinfunction "1_1") (pintype "input"))
      (node (ref "U36") (pin "2") (pinfunction "CS_2") (pintype "input"))
    )
    (net (code "108") (name "Net-(U36-GND)") (class "Default")
      (node (ref "C49") (pin "1") (pinfunction "1_1") (pintype "input"))
      (node (ref "H7") (pin "1") (pinfunction "1_1") (pintype "unspecified"))
      (node (ref "U36") (pin "6") (pinfunction "GND_6") (pintype "input"))
      (node (ref "U38") (pin "2") (pinfunction "S_2") (pintype "input"))
    )
    (net (code "109") (name "Net-(U36-OC)") (class "Default")
      (node (ref "U36") (pin "3") (pinfunction "OC_3") (pintype "input"))
      (node (ref "U37") (pin "1") (pinfunction "G_1") (pintype "input"))
    )
    (net (code "110") (name "Net-(U36-OD)") (class "Default")
      (node (ref "U36") (pin "1") (pinfunction "OD_1") (pintype "input"))
      (node (ref "U38") (pin "1") (pinfunction "G_1") (pintype "input"))
    )
    (net (code "111") (name "Net-(U36-VCC)") (class "Default")
      (node (ref "C49") (pin "2") (pinfunction "2_2") (pintype "input"))
      (node (ref "R84") (pin "2") (pinfunction "2_2") (pintype "input"))
      (node (ref "U36") (pin "5") (pinfunction "VCC_5") (pintype "input"))
    )
    (net (code "112") (name "Net-(U37-D)") (class "Default")
      (node (ref "U37") (pin "3") (pinfunction "D_3") (pintype "input"))
      (node (ref "U38") (pin "3") (pinfunction "D_3") (pintype "input"))
    )
    (net (code "113") (name "Net-(USB1-CC1)") (class "Default")
      (node (ref "R78") (pin "2") (pinfunction "2_2") (pintype "input"))
      (node (ref "USB1") (pin "4") (pinfunction "CC1_4") (pintype "input"))
    )
    (net (code "114") (name "Net-(USB1-CC2)") (class "Default")
      (node (ref "R79") (pin "2") (pinfunction "2_2") (pintype "input"))
      (node (ref "USB1") (pin "10") (pinfunction "CC2_10") (pintype "input"))
    )
    (net (code "115") (name "unconnected-(LCD1-DB0-Pad7)") (class "Default")
      (node (ref "LCD1") (pin "7") (pinfunction "DB0_7") (pintype "input+no_connect"))
    )
    (net (code "116") (name "unconnected-(LCD1-DB1-Pad8)") (class "Default")
      (node (ref "LCD1") (pin "8") (pinfunction "DB1_8") (pintype "input+no_connect"))
    )
    (net (code "117") (name "unconnected-(LCD1-DB2-Pad9)") (class "Default")
      (node (ref "LCD1") (pin "9") (pinfunction "DB2_9") (pintype "input+no_connect"))
    )
    (net (code "118") (name "unconnected-(LCD1-DB3-Pad10)") (class "Default")
      (node (ref "LCD1") (pin "10") (pinfunction "DB3_10") (pintype "input+no_connect"))
    )
    (net (code "119") (name "unconnected-(U32-Q6-Pad6)") (class "Default")
      (node (ref "U32") (pin "6") (pinfunction "Q6_6") (pintype "input"))
    )
    (net (code "120") (name "unconnected-(U32-Q7&apos;-Pad9)") (class "Default")
      (node (ref "U32") (pin "9") (pinfunction "Q7&apos;_9") (pintype "input"))
    )
    (net (code "121") (name "unconnected-(U32-Q7-Pad7)") (class "Default")
      (node (ref "U32") (pin "7") (pinfunction "Q7_7") (pintype "input"))
    )
    (net (code "122") (name "unconnected-(U36-TD-Pad4)") (class "Default")
      (node (ref "U36") (pin "4") (pinfunction "TD_4") (pintype "input+no_connect"))
    )
    (net (code "123") (name "unconnected-(USB1-DN1-Pad7)") (class "Default")
      (node (ref "USB1") (pin "7") (pinfunction "DN1_7") (pintype "input+no_connect"))
    )
    (net (code "124") (name "unconnected-(USB1-DN2-Pad5)") (class "Default")
      (node (ref "USB1") (pin "5") (pinfunction "DN2_5") (pintype "input+no_connect"))
    )
    (net (code "125") (name "unconnected-(USB1-DP1-Pad6)") (class "Default")
      (node (ref "USB1") (pin "6") (pinfunction "DP1_6") (pintype "input+no_connect"))
    )
    (net (code "126") (name "unconnected-(USB1-DP2-Pad8)") (class "Default")
      (node (ref "USB1") (pin "8") (pinfunction "DP2_8") (pintype "input+no_connect"))
    )
    (net (code "127") (name "unconnected-(USB1-SBU1-Pad9)") (class "Default")
      (node (ref "USB1") (pin "9") (pinfunction "SBU1_9") (pintype "input+no_connect"))
    )
    (net (code "128") (name "unconnected-(USB1-SBU2-Pad3)") (class "Default")
      (node (ref "USB1") (pin "3") (pinfunction "SBU2_3") (pintype "input+no_connect"))
    )
  )
)
